# rings_v30.net
KiCad netlist of a schematic drawn in EAGLE
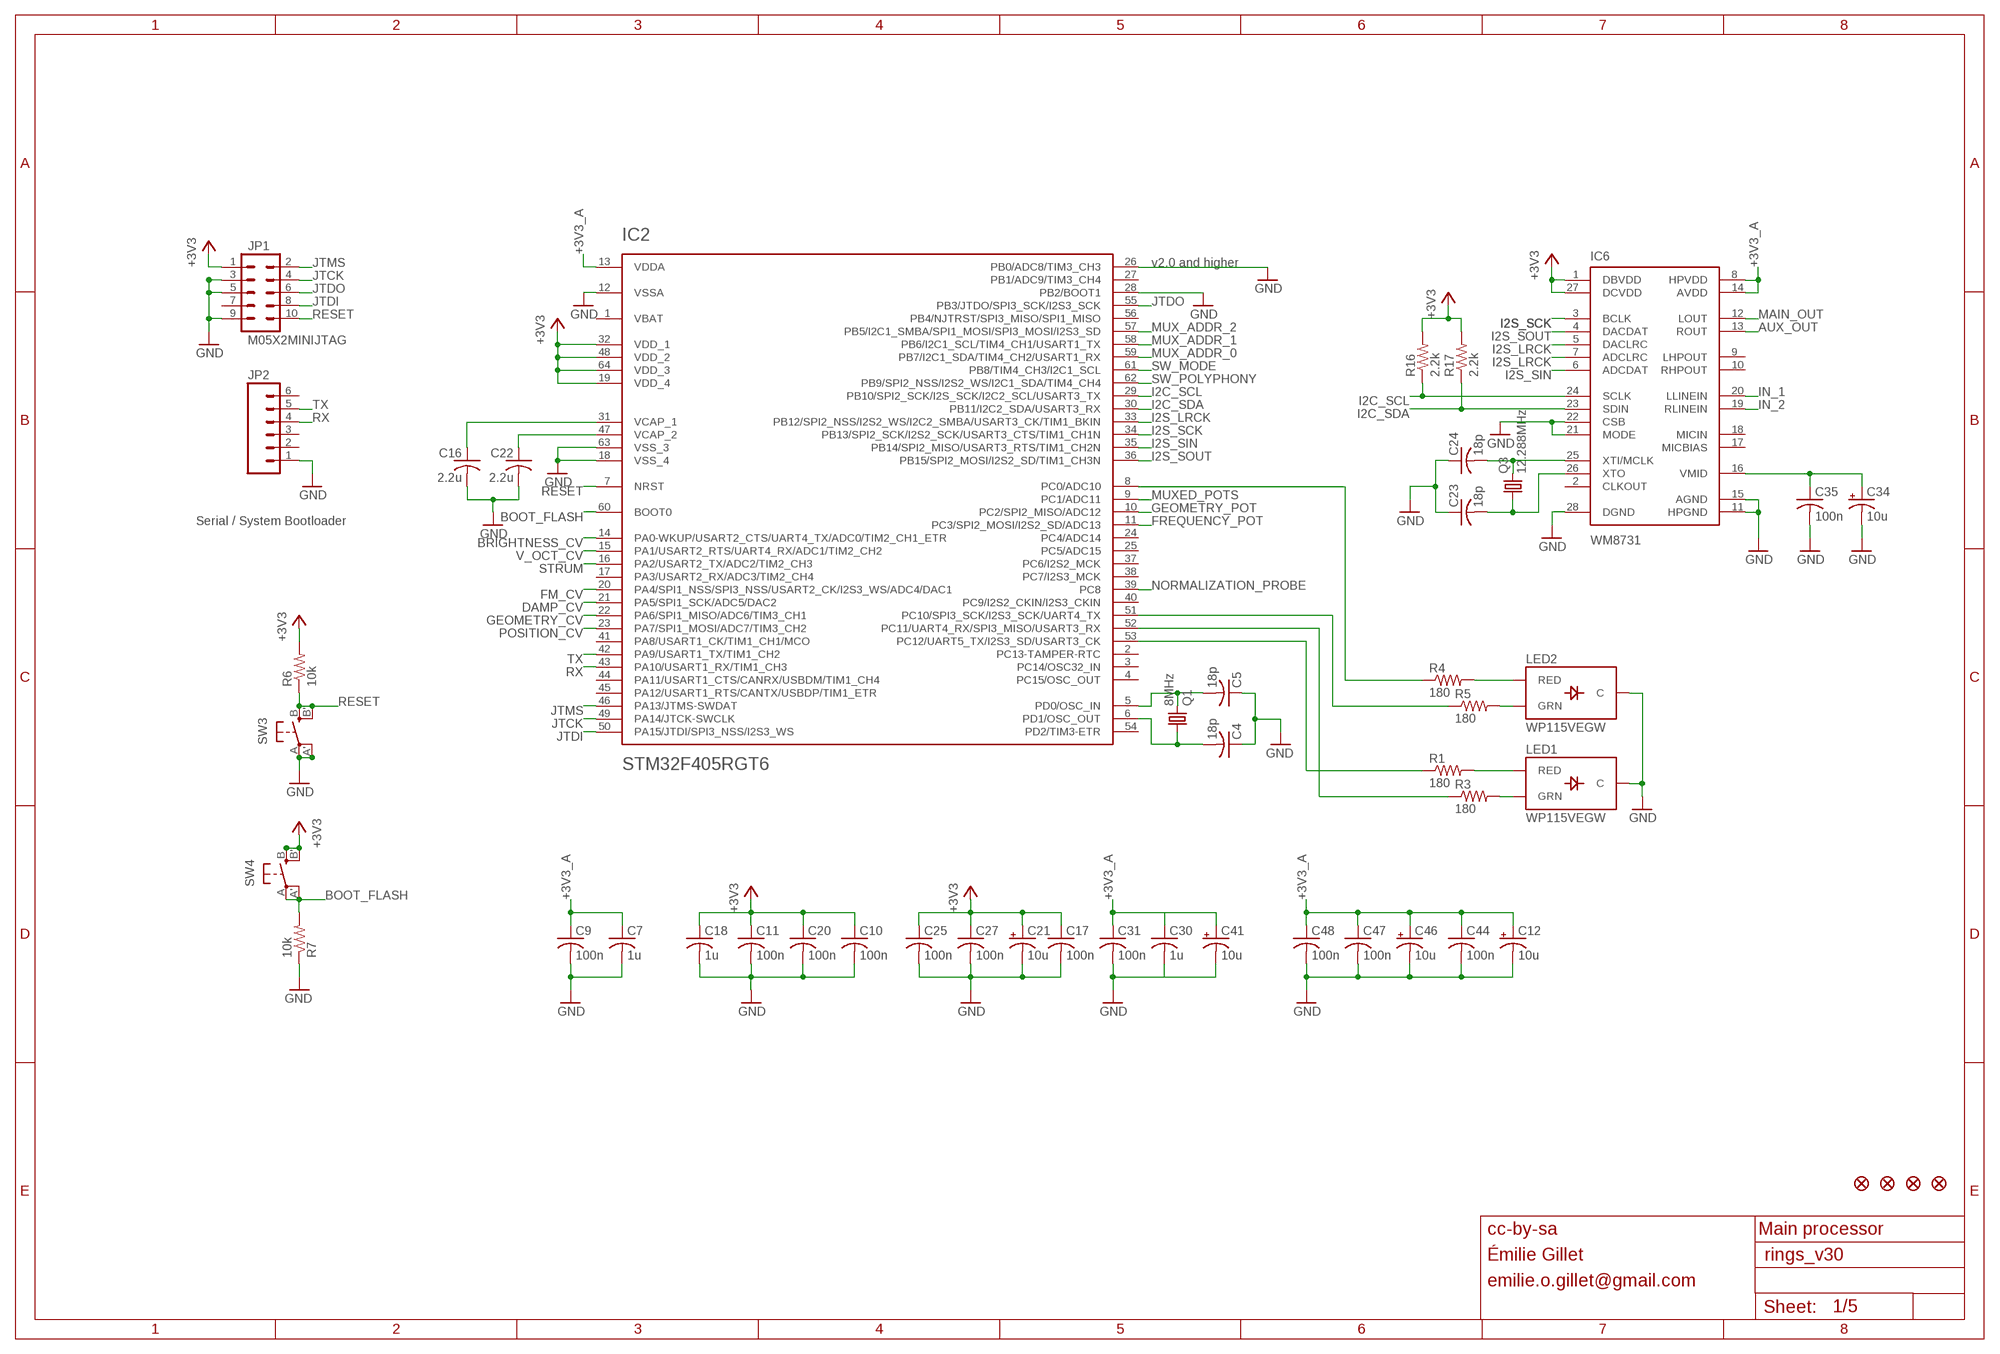
[diagram p0: schematic, sheet 1]
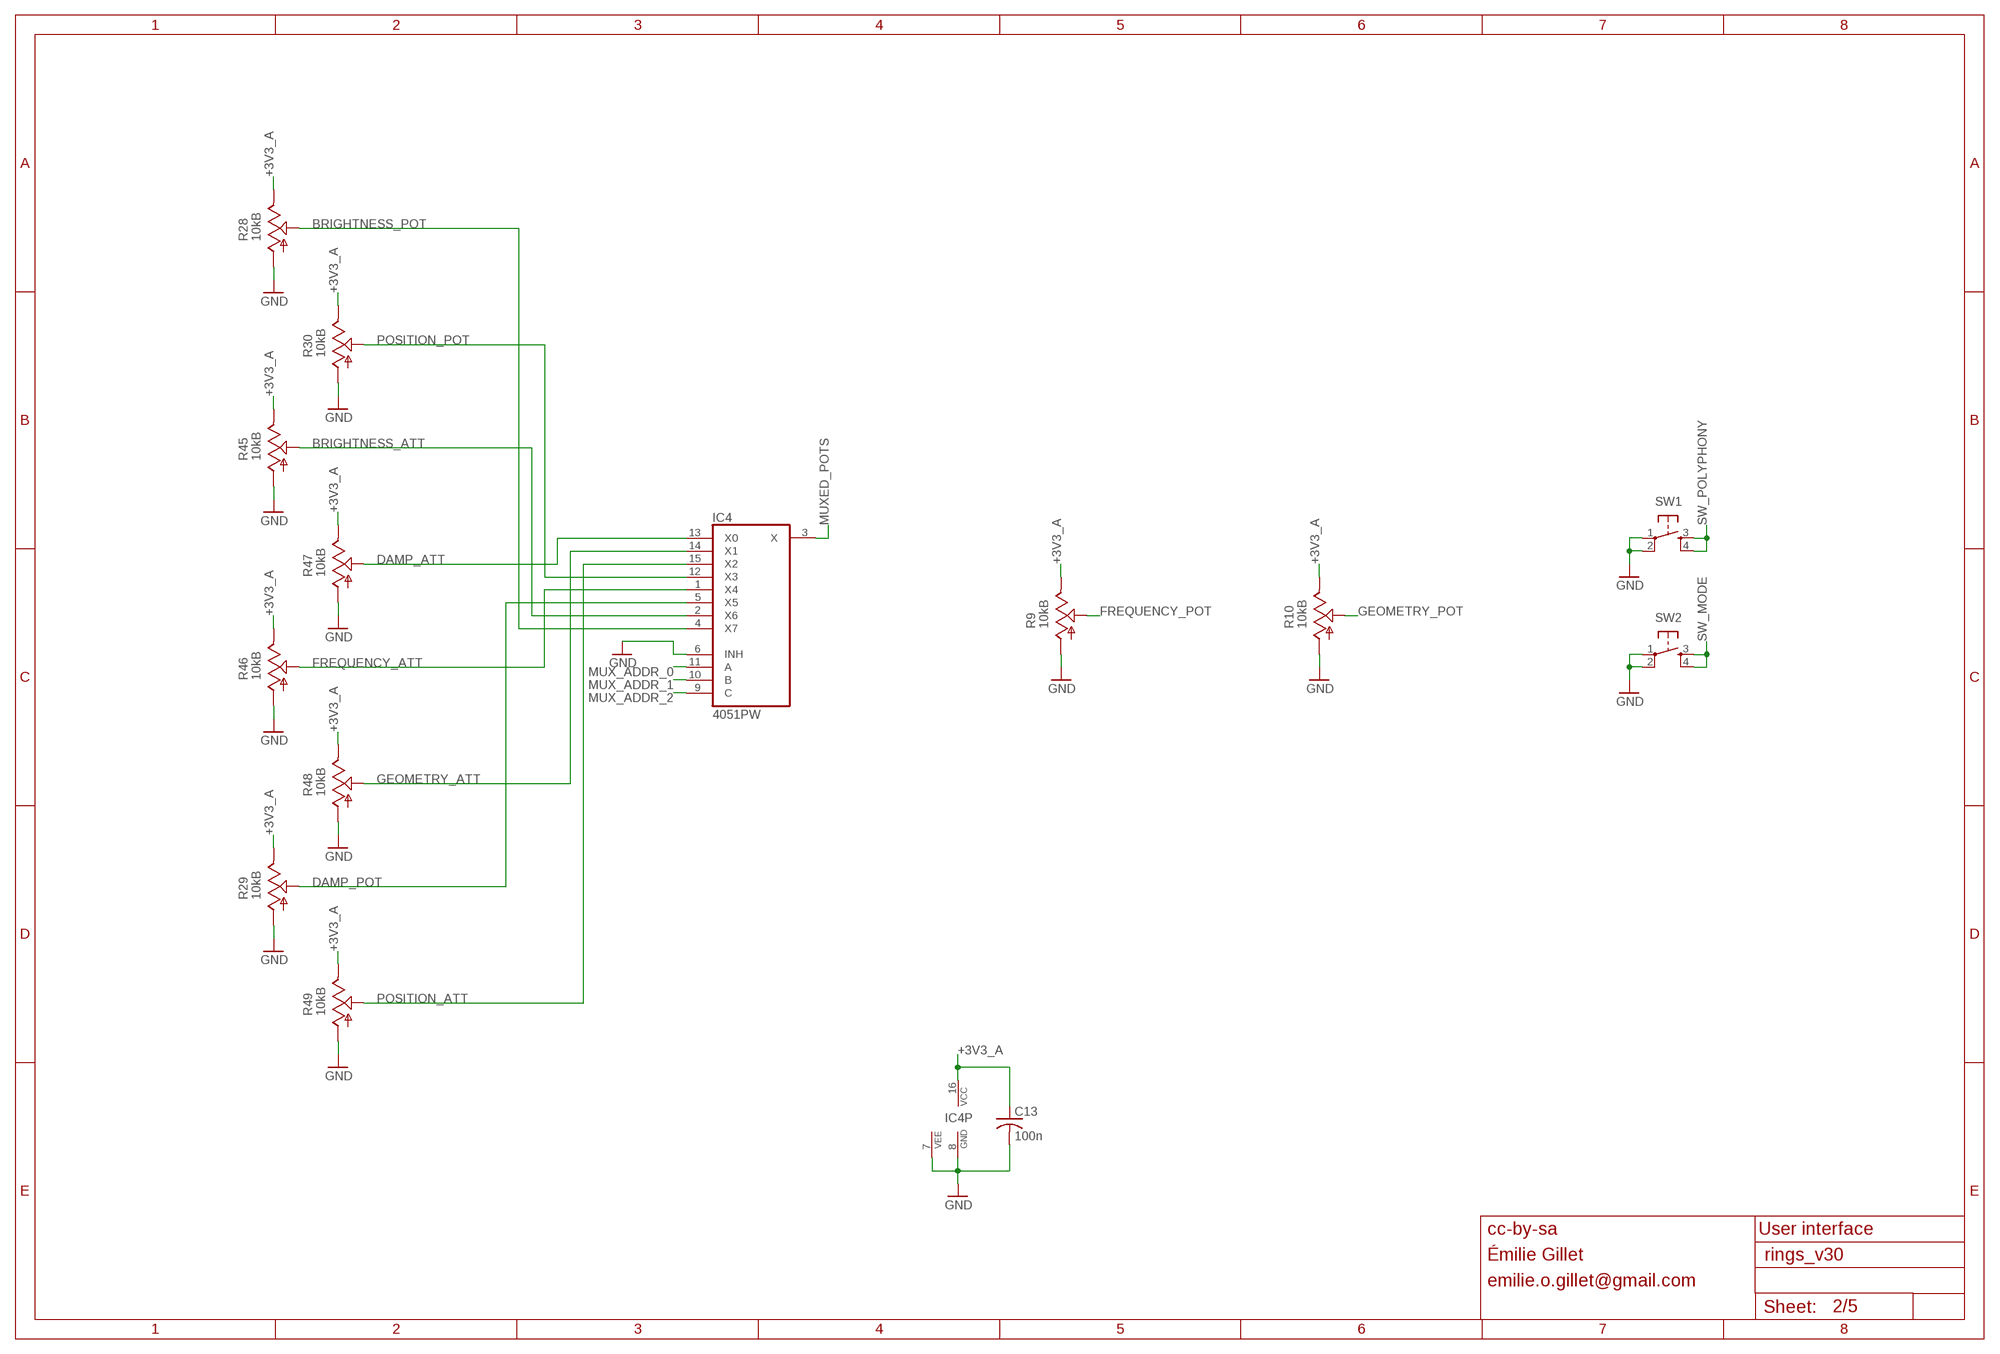
[diagram p1: schematic, sheet 2]
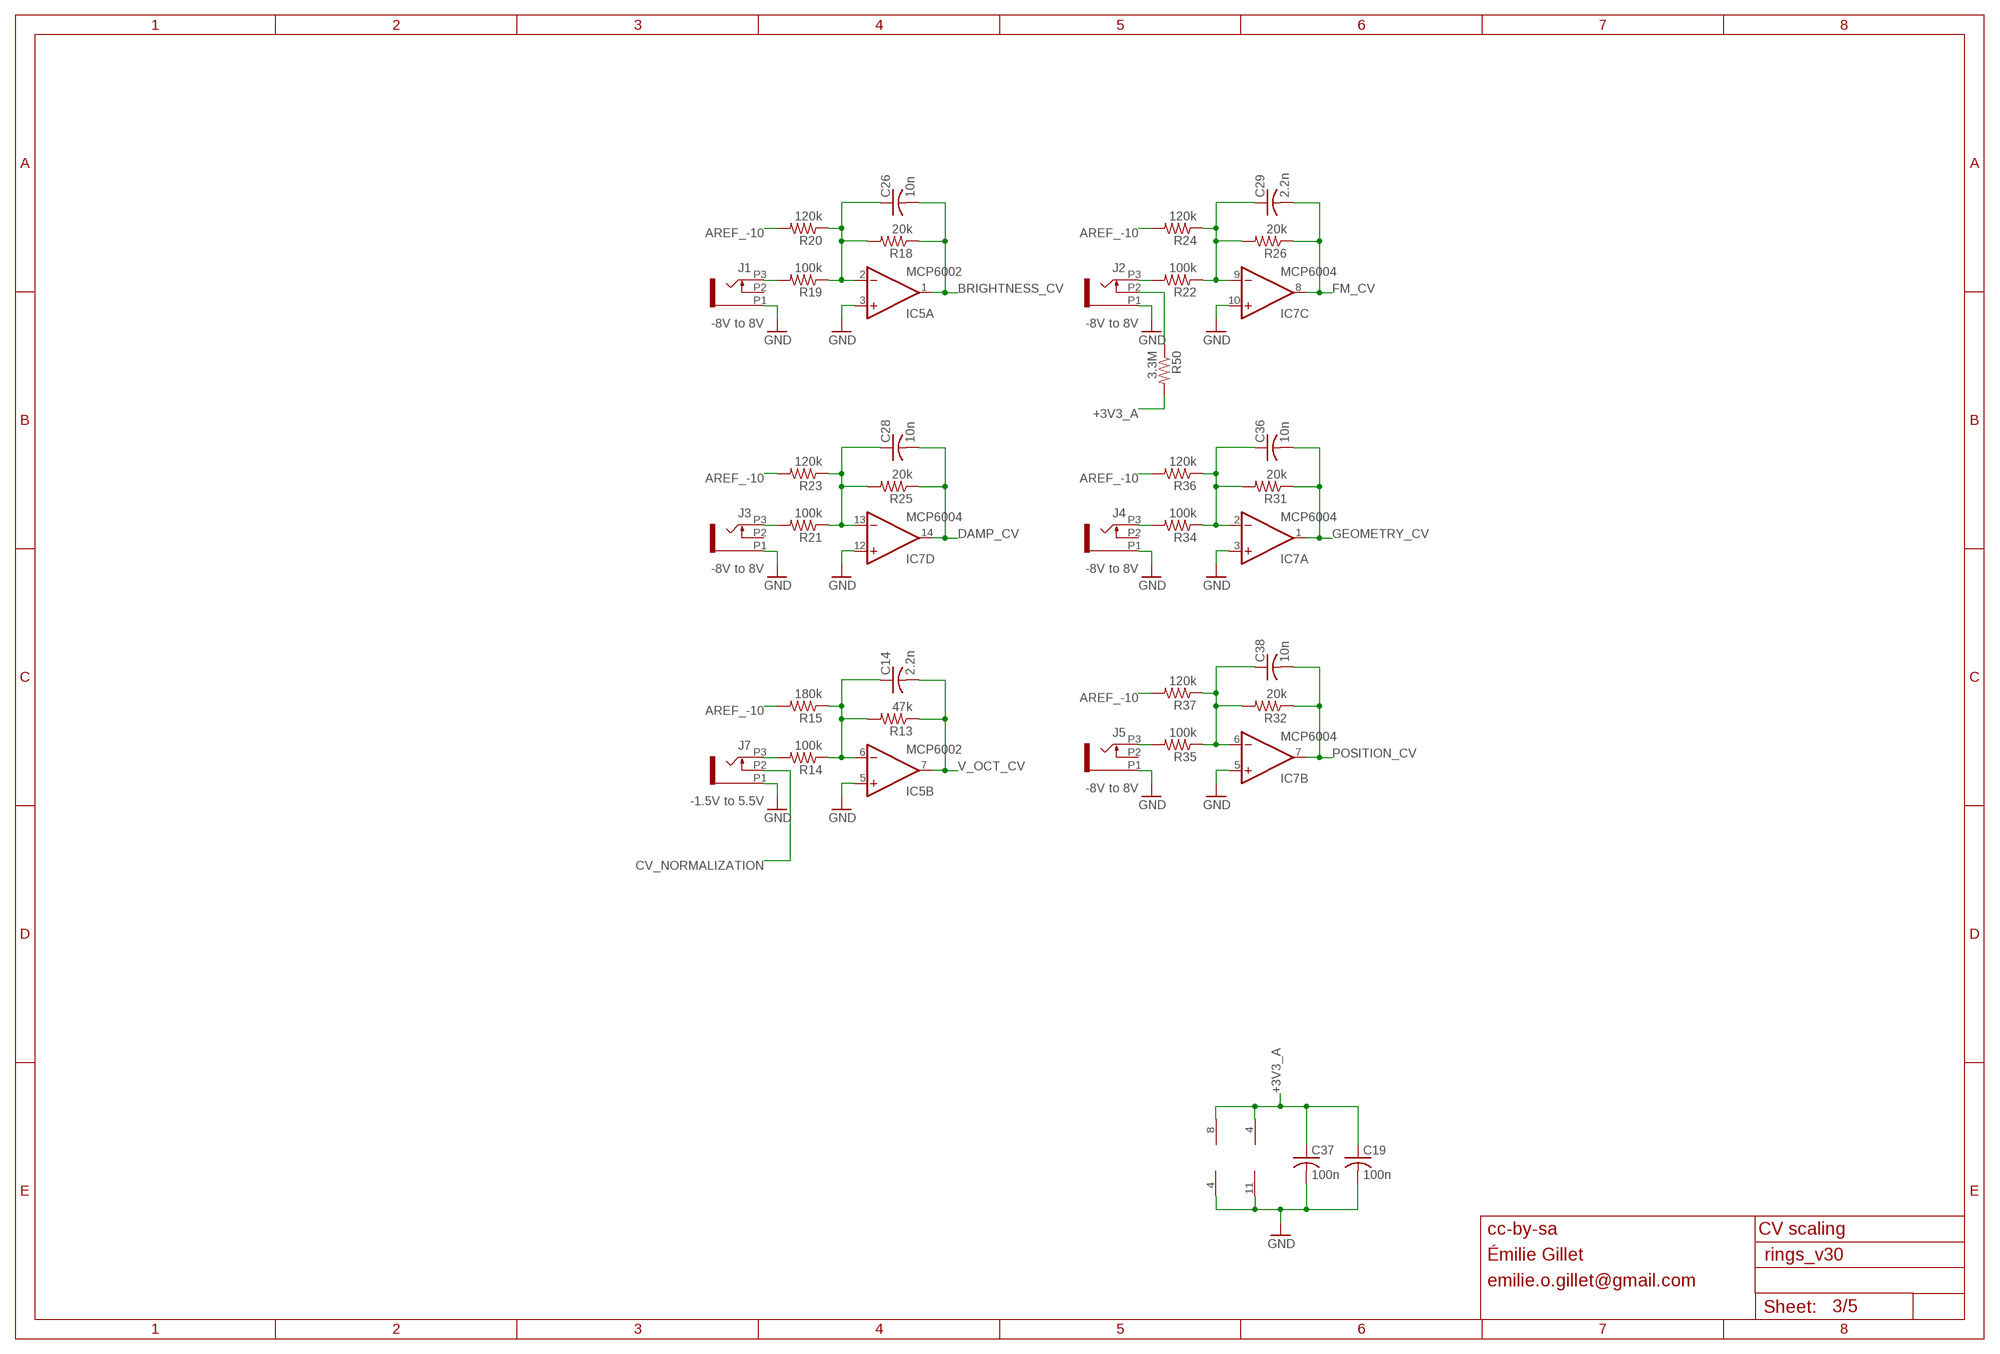
[diagram p2: schematic, sheet 3]
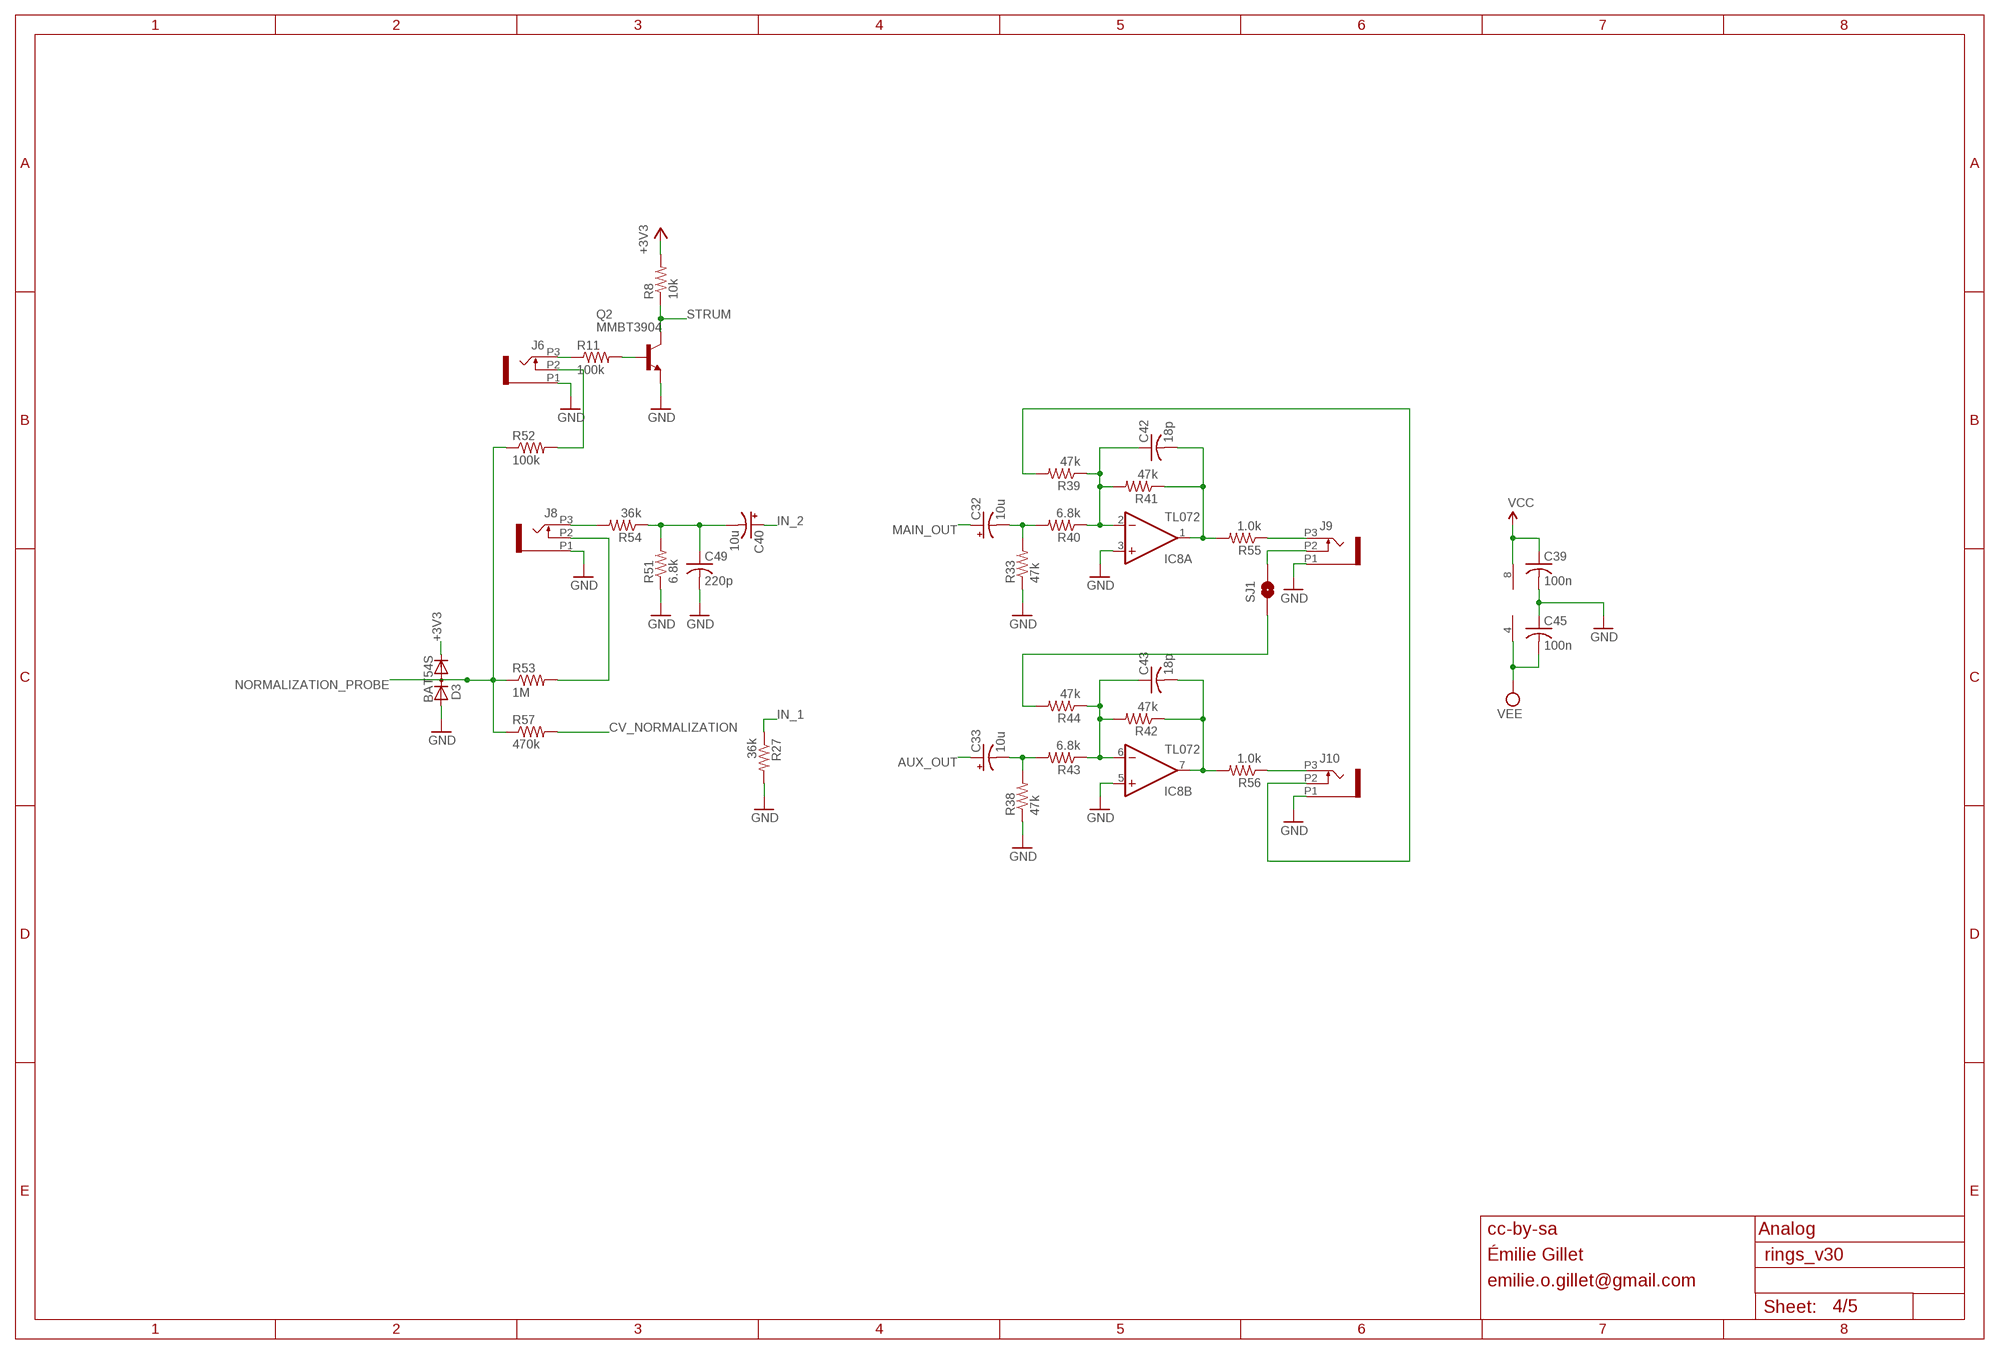
[diagram p3: schematic, sheet 4]
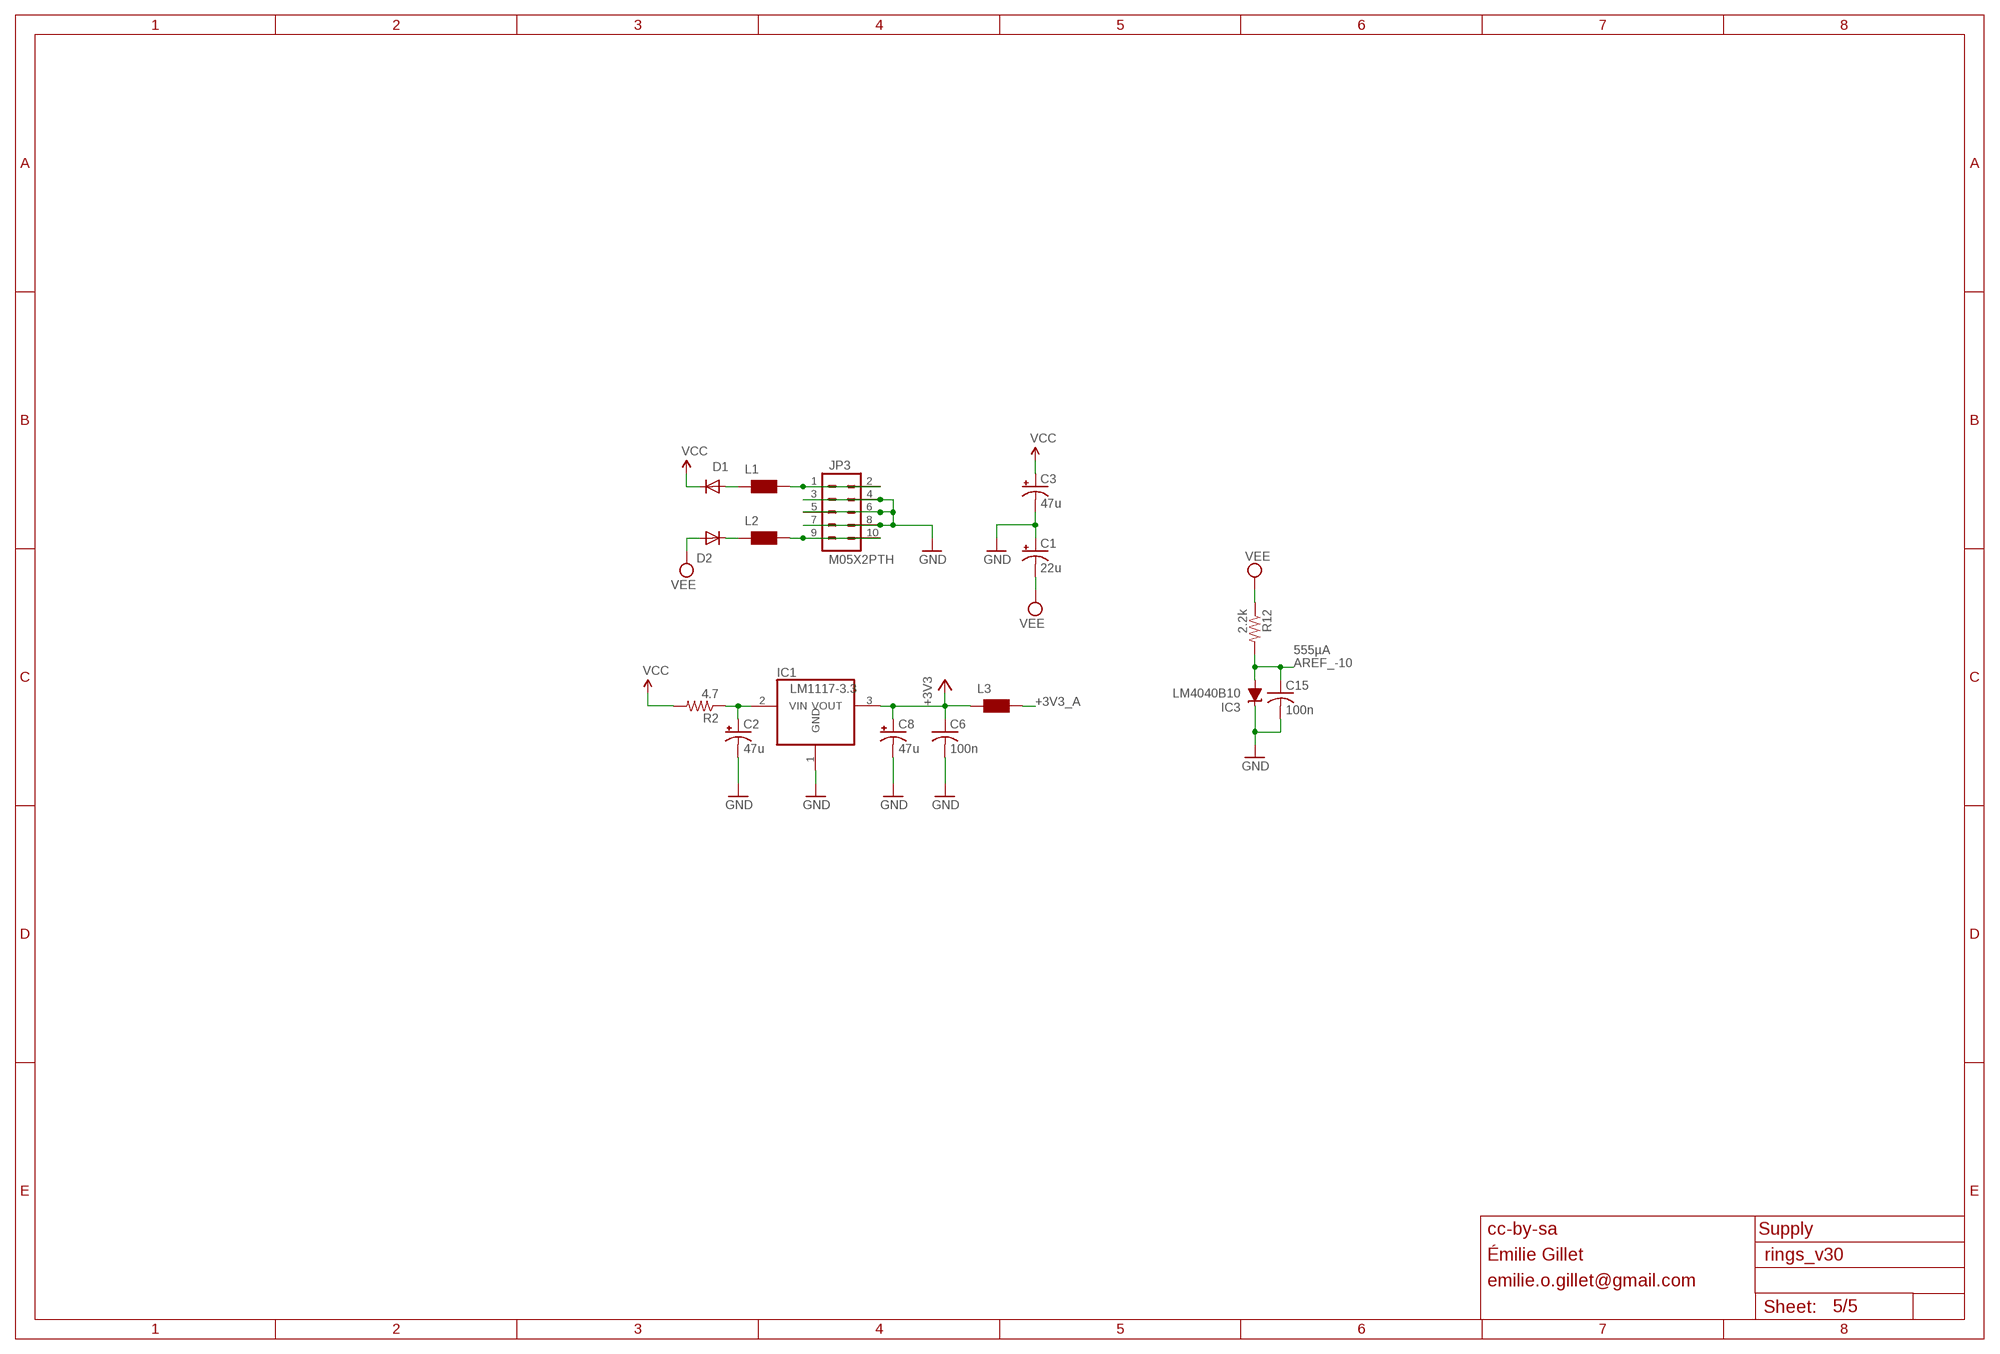
[diagram p4: schematic, sheet 5]

(export (version "E")
  (design (tool "Eeschema 10.0.6"))
  (components
    (comp (ref "C14")
      (value "2.2n")
      (footprint "eagle-import:C0603")
      (libsource (lib "eagle-import") (part "C-USC0603"))
    )
    (comp (ref "C19")
      (value "100n")
      (footprint "eagle-import:C0603")
      (libsource (lib "eagle-import") (part "C-USC0603"))
    )
    (comp (ref "C26")
      (value "10n")
      (footprint "eagle-import:C0603")
      (libsource (lib "eagle-import") (part "C-USC0603"))
    )
    (comp (ref "C28")
      (value "10n")
      (footprint "eagle-import:C0603")
      (libsource (lib "eagle-import") (part "C-USC0603"))
    )
    (comp (ref "C29")
      (value "2.2n")
      (footprint "eagle-import:C0603")
      (libsource (lib "eagle-import") (part "C-USC0603"))
    )
    (comp (ref "C36")
      (value "10n")
      (footprint "eagle-import:C0603")
      (libsource (lib "eagle-import") (part "C-USC0603"))
    )
    (comp (ref "C37")
      (value "100n")
      (footprint "eagle-import:C0603")
      (libsource (lib "eagle-import") (part "C-USC0603"))
    )
    (comp (ref "C38")
      (value "10n")
      (footprint "eagle-import:C0603")
      (libsource (lib "eagle-import") (part "C-USC0603"))
    )
    (comp (ref "IC5")
      (value "MCP6002")
      (footprint "eagle-import:SO08")
      (libsource (lib "eagle-import") (part "TL072D"))
    )
    (comp (ref "IC7")
      (value "MCP6004")
      (footprint "eagle-import:SO14")
      (libsource (lib "eagle-import") (part "TL074D"))
    )
    (comp (ref "J1")
      (value "PJ301_THONKICONN6")
      (footprint "eagle-import:WQP_PJ_301M6")
      (libsource (lib "eagle-import") (part "PJ301_THONKICONN6"))
    )
    (comp (ref "J2")
      (value "PJ301_THONKICONN6")
      (footprint "eagle-import:WQP_PJ_301M6")
      (libsource (lib "eagle-import") (part "PJ301_THONKICONN6"))
    )
    (comp (ref "J3")
      (value "PJ301_THONKICONN6")
      (footprint "eagle-import:WQP_PJ_301M6")
      (libsource (lib "eagle-import") (part "PJ301_THONKICONN6"))
    )
    (comp (ref "J4")
      (value "PJ301_THONKICONN6")
      (footprint "eagle-import:WQP_PJ_301M6")
      (libsource (lib "eagle-import") (part "PJ301_THONKICONN6"))
    )
    (comp (ref "J5")
      (value "PJ301_THONKICONN6")
      (footprint "eagle-import:WQP_PJ_301M6")
      (libsource (lib "eagle-import") (part "PJ301_THONKICONN6"))
    )
    (comp (ref "J7")
      (value "PJ301_THONKICONN6")
      (footprint "eagle-import:WQP_PJ_301M6")
      (libsource (lib "eagle-import") (part "PJ301_THONKICONN6"))
    )
    (comp (ref "R13")
      (value "47k")
      (footprint "eagle-import:R0603")
      (libsource (lib "eagle-import") (part "R-US_R0603"))
    )
    (comp (ref "R14")
      (value "100k")
      (footprint "eagle-import:R0603")
      (libsource (lib "eagle-import") (part "R-US_R0603"))
    )
    (comp (ref "R15")
      (value "180k")
      (footprint "eagle-import:R0603")
      (libsource (lib "eagle-import") (part "R-US_R0603"))
    )
    (comp (ref "R18")
      (value "20k")
      (footprint "eagle-import:R0603")
      (libsource (lib "eagle-import") (part "R-US_R0603"))
    )
    (comp (ref "R19")
      (value "100k")
      (footprint "eagle-import:R0603")
      (libsource (lib "eagle-import") (part "R-US_R0603"))
    )
    (comp (ref "R20")
      (value "120k")
      (footprint "eagle-import:R0603")
      (libsource (lib "eagle-import") (part "R-US_R0603"))
    )
    (comp (ref "R21")
      (value "100k")
      (footprint "eagle-import:R0603")
      (libsource (lib "eagle-import") (part "R-US_R0603"))
    )
    (comp (ref "R22")
      (value "100k")
      (footprint "eagle-import:R0603")
      (libsource (lib "eagle-import") (part "R-US_R0603"))
    )
    (comp (ref "R23")
      (value "120k")
      (footprint "eagle-import:R0603")
      (libsource (lib "eagle-import") (part "R-US_R0603"))
    )
    (comp (ref "R24")
      (value "120k")
      (footprint "eagle-import:R0603")
      (libsource (lib "eagle-import") (part "R-US_R0603"))
    )
    (comp (ref "R25")
      (value "20k")
      (footprint "eagle-import:R0603")
      (libsource (lib "eagle-import") (part "R-US_R0603"))
    )
    (comp (ref "R26")
      (value "20k")
      (footprint "eagle-import:R0603")
      (libsource (lib "eagle-import") (part "R-US_R0603"))
    )
    (comp (ref "R31")
      (value "20k")
      (footprint "eagle-import:R0603")
      (libsource (lib "eagle-import") (part "R-US_R0603"))
    )
    (comp (ref "R32")
      (value "20k")
      (footprint "eagle-import:R0603")
      (libsource (lib "eagle-import") (part "R-US_R0603"))
    )
    (comp (ref "R34")
      (value "100k")
      (footprint "eagle-import:R0603")
      (libsource (lib "eagle-import") (part "R-US_R0603"))
    )
    (comp (ref "R35")
      (value "100k")
      (footprint "eagle-import:R0603")
      (libsource (lib "eagle-import") (part "R-US_R0603"))
    )
    (comp (ref "R36")
      (value "120k")
      (footprint "eagle-import:R0603")
      (libsource (lib "eagle-import") (part "R-US_R0603"))
    )
    (comp (ref "R37")
      (value "120k")
      (footprint "eagle-import:R0603")
      (libsource (lib "eagle-import") (part "R-US_R0603"))
    )
    (comp (ref "R50")
      (value "3.3M")
      (footprint "eagle-import:R0603")
      (libsource (lib "eagle-import") (part "R-US_R0603"))
    )
    (comp (ref "C13")
      (value "100n")
      (footprint "eagle-import:C0603")
      (libsource (lib "eagle-import") (part "C-USC0603"))
    )
    (comp (ref "IC4")
      (value "4051PW")
      (footprint "eagle-import:TSSOP16")
      (libsource (lib "eagle-import") (part "4051PW"))
    )
    (comp (ref "R9")
      (value "10kB")
      (footprint "eagle-import:ALPS_POT_VERTICAL_PS")
      (libsource (lib "eagle-import") (part "POT_USVERTICAL_PS"))
    )
    (comp (ref "R10")
      (value "10kB")
      (footprint "eagle-import:ALPS_POT_VERTICAL_PS")
      (libsource (lib "eagle-import") (part "POT_USVERTICAL_PS"))
    )
    (comp (ref "R28")
      (value "10kB")
      (footprint "eagle-import:ALPS_POT_VERTICAL_PS")
      (libsource (lib "eagle-import") (part "POT_USVERTICAL_PS"))
    )
    (comp (ref "R29")
      (value "10kB")
      (footprint "eagle-import:ALPS_POT_VERTICAL_PS")
      (libsource (lib "eagle-import") (part "POT_USVERTICAL_PS"))
    )
    (comp (ref "R30")
      (value "10kB")
      (footprint "eagle-import:ALPS_POT_VERTICAL_PS")
      (libsource (lib "eagle-import") (part "POT_USVERTICAL_PS"))
    )
    (comp (ref "R45")
      (value "10kB")
      (footprint "eagle-import:ALPS_POT_VERTICAL")
      (libsource (lib "eagle-import") (part "POT_USVERTICAL"))
    )
    (comp (ref "R46")
      (value "10kB")
      (footprint "eagle-import:ALPS_POT_VERTICAL")
      (libsource (lib "eagle-import") (part "POT_USVERTICAL"))
    )
    (comp (ref "R47")
      (value "10kB")
      (footprint "eagle-import:ALPS_POT_VERTICAL")
      (libsource (lib "eagle-import") (part "POT_USVERTICAL"))
    )
    (comp (ref "R48")
      (value "10kB")
      (footprint "eagle-import:ALPS_POT_VERTICAL")
      (libsource (lib "eagle-import") (part "POT_USVERTICAL"))
    )
    (comp (ref "R49")
      (value "10kB")
      (footprint "eagle-import:ALPS_POT_VERTICAL")
      (libsource (lib "eagle-import") (part "POT_USVERTICAL"))
    )
    (comp (ref "SW1")
      (value "TAC_SWITCHPTH")
      (footprint "eagle-import:TACTILE-PTH")
      (libsource (lib "eagle-import") (part "TAC_SWITCHPTH"))
    )
    (comp (ref "SW2")
      (value "TAC_SWITCHPTH")
      (footprint "eagle-import:TACTILE-PTH")
      (libsource (lib "eagle-import") (part "TAC_SWITCHPTH"))
    )
    (comp (ref "C1")
      (value "22u")
      (footprint "eagle-import:PANASONIC_C")
      (libsource (lib "eagle-import") (part "CPOL-USC"))
    )
    (comp (ref "C2")
      (value "47u")
      (footprint "eagle-import:PANASONIC_D")
      (libsource (lib "eagle-import") (part "CPOL-USD"))
    )
    (comp (ref "C3")
      (value "47u")
      (footprint "eagle-import:PANASONIC_D")
      (libsource (lib "eagle-import") (part "CPOL-USD"))
    )
    (comp (ref "C6")
      (value "100n")
      (footprint "eagle-import:C0603")
      (libsource (lib "eagle-import") (part "C-USC0603"))
    )
    (comp (ref "C8")
      (value "47u")
      (footprint "eagle-import:PANASONIC_D")
      (libsource (lib "eagle-import") (part "CPOL-USD"))
    )
    (comp (ref "C15")
      (value "100n")
      (footprint "eagle-import:C0603")
      (libsource (lib "eagle-import") (part "C-USC0603"))
    )
    (comp (ref "D1")
      (value "1N5819HW")
      (footprint "eagle-import:SOD123")
      (libsource (lib "eagle-import") (part "DIODE-SOD123"))
    )
    (comp (ref "D2")
      (value "1N5819HW")
      (footprint "eagle-import:SOD123")
      (libsource (lib "eagle-import") (part "DIODE-SOD123"))
    )
    (comp (ref "IC1")
      (value "LM1117-3.3")
      (footprint "eagle-import:TO252")
      (libsource (lib "eagle-import") (part "REG1117T"))
    )
    (comp (ref "IC3")
      (value "LM4040B10")
      (footprint "eagle-import:DBZ_R-PDSO-G3")
      (libsource (lib "eagle-import") (part "LM4041DBZB12"))
    )
    (comp (ref "JP3")
      (value "M05X2PTH")
      (footprint "eagle-import:AVR_ICSP")
      (libsource (lib "eagle-import") (part "M05X2PTH"))
    )
    (comp (ref "L1")
      (value "WE-CBF_0603")
      (footprint "eagle-import:0603")
      (libsource (lib "eagle-import") (part "WE-CBF_0603"))
    )
    (comp (ref "L2")
      (value "WE-CBF_0603")
      (footprint "eagle-import:0603")
      (libsource (lib "eagle-import") (part "WE-CBF_0603"))
    )
    (comp (ref "L3")
      (value "WE-CBF_0603")
      (footprint "eagle-import:0603")
      (libsource (lib "eagle-import") (part "WE-CBF_0603"))
    )
    (comp (ref "R2")
      (value "4.7")
      (footprint "eagle-import:R1206")
      (libsource (lib "eagle-import") (part "R-US_R1206"))
    )
    (comp (ref "R12")
      (value "2.2k")
      (footprint "eagle-import:R0603")
      (libsource (lib "eagle-import") (part "R-US_R0603"))
    )
    (comp (ref "C4")
      (value "18p")
      (footprint "eagle-import:C0603")
      (libsource (lib "eagle-import") (part "C-USC0603"))
    )
    (comp (ref "C5")
      (value "18p")
      (footprint "eagle-import:C0603")
      (libsource (lib "eagle-import") (part "C-USC0603"))
    )
    (comp (ref "C7")
      (value "1u")
      (footprint "eagle-import:C0603")
      (libsource (lib "eagle-import") (part "C-USC0603"))
    )
    (comp (ref "C9")
      (value "100n")
      (footprint "eagle-import:C0603")
      (libsource (lib "eagle-import") (part "C-USC0603"))
    )
    (comp (ref "C10")
      (value "100n")
      (footprint "eagle-import:C0603")
      (libsource (lib "eagle-import") (part "C-USC0603"))
    )
    (comp (ref "C11")
      (value "100n")
      (footprint "eagle-import:C0603")
      (libsource (lib "eagle-import") (part "C-USC0603"))
    )
    (comp (ref "C12")
      (value "10u")
      (footprint "eagle-import:PANASONIC_A")
      (libsource (lib "eagle-import") (part "CPOL-USA"))
    )
    (comp (ref "C16")
      (value "2.2u")
      (footprint "eagle-import:C0805")
      (libsource (lib "eagle-import") (part "C-USC0805"))
    )
    (comp (ref "C17")
      (value "100n")
      (footprint "eagle-import:C0603")
      (libsource (lib "eagle-import") (part "C-USC0603"))
    )
    (comp (ref "C18")
      (value "1u")
      (footprint "eagle-import:C0603")
      (libsource (lib "eagle-import") (part "C-USC0603"))
    )
    (comp (ref "C20")
      (value "100n")
      (footprint "eagle-import:C0603")
      (libsource (lib "eagle-import") (part "C-USC0603"))
    )
    (comp (ref "C21")
      (value "10u")
      (footprint "eagle-import:PANASONIC_A")
      (libsource (lib "eagle-import") (part "CPOL-USA"))
    )
    (comp (ref "C22")
      (value "2.2u")
      (footprint "eagle-import:C0805")
      (libsource (lib "eagle-import") (part "C-USC0805"))
    )
    (comp (ref "C23")
      (value "18p")
      (footprint "eagle-import:C0603")
      (libsource (lib "eagle-import") (part "C-USC0603"))
    )
    (comp (ref "C24")
      (value "18p")
      (footprint "eagle-import:C0603")
      (libsource (lib "eagle-import") (part "C-USC0603"))
    )
    (comp (ref "C25")
      (value "100n")
      (footprint "eagle-import:C0603")
      (libsource (lib "eagle-import") (part "C-USC0603"))
    )
    (comp (ref "C27")
      (value "100n")
      (footprint "eagle-import:C0603")
      (libsource (lib "eagle-import") (part "C-USC0603"))
    )
    (comp (ref "C30")
      (value "1u")
      (footprint "eagle-import:C0603")
      (libsource (lib "eagle-import") (part "C-USC0603"))
    )
    (comp (ref "C31")
      (value "100n")
      (footprint "eagle-import:C0603")
      (libsource (lib "eagle-import") (part "C-USC0603"))
    )
    (comp (ref "C34")
      (value "10u")
      (footprint "eagle-import:PANASONIC_A")
      (libsource (lib "eagle-import") (part "CPOL-USA"))
    )
    (comp (ref "C35")
      (value "100n")
      (footprint "eagle-import:C0603")
      (libsource (lib "eagle-import") (part "C-USC0603"))
    )
    (comp (ref "C41")
      (value "10u")
      (footprint "eagle-import:PANASONIC_A")
      (libsource (lib "eagle-import") (part "CPOL-USA"))
    )
    (comp (ref "C44")
      (value "100n")
      (footprint "eagle-import:C0603")
      (libsource (lib "eagle-import") (part "C-USC0603"))
    )
    (comp (ref "C46")
      (value "10u")
      (footprint "eagle-import:PANASONIC_A")
      (libsource (lib "eagle-import") (part "CPOL-USA"))
    )
    (comp (ref "C47")
      (value "100n")
      (footprint "eagle-import:C0603")
      (libsource (lib "eagle-import") (part "C-USC0603"))
    )
    (comp (ref "C48")
      (value "100n")
      (footprint "eagle-import:C0603")
      (libsource (lib "eagle-import") (part "C-USC0603"))
    )
    (comp (ref "F1")
      (value "FIDUCIAL1X2")
      (footprint "eagle-import:FIDUCIAL-1X2")
      (libsource (lib "eagle-import") (part "FIDUCIAL1X2"))
    )
    (comp (ref "F2")
      (value "FIDUCIAL1X2")
      (footprint "eagle-import:FIDUCIAL-1X2")
      (libsource (lib "eagle-import") (part "FIDUCIAL1X2"))
    )
    (comp (ref "F3")
      (value "FIDUCIAL1X2")
      (footprint "eagle-import:FIDUCIAL-1X2")
      (libsource (lib "eagle-import") (part "FIDUCIAL1X2"))
    )
    (comp (ref "F4")
      (value "FIDUCIAL1X2")
      (footprint "eagle-import:FIDUCIAL-1X2")
      (libsource (lib "eagle-import") (part "FIDUCIAL1X2"))
    )
    (comp (ref "IC2")
      (value "STM32F405RGT6")
      (footprint "eagle-import:TQFP-10X10-64")
      (libsource (lib "eagle-import") (part "STM32F20X"))
    )
    (comp (ref "IC6")
      (value "WM8731")
      (footprint "eagle-import:SSOP28")
      (libsource (lib "eagle-import") (part "WM8731"))
    )
    (comp (ref "JP1")
      (value "M05X2MINIJTAG")
      (footprint "eagle-import:2X5-1.27")
      (libsource (lib "eagle-import") (part "M05X2MINIJTAG"))
    )
    (comp (ref "JP2")
      (value "M06SIP")
      (footprint "eagle-import:1X06")
      (libsource (lib "eagle-import") (part "M06SIP"))
    )
    (comp (ref "LED1")
      (value "WP115VEGW")
      (footprint "eagle-import:LED-BICOLOR-THROUGHHOLE")
      (libsource (lib "eagle-import") (part "LED-BICOLOR-THROUGHHOLE"))
    )
    (comp (ref "LED2")
      (value "WP115VEGW")
      (footprint "eagle-import:LED-BICOLOR-THROUGHHOLE")
      (libsource (lib "eagle-import") (part "LED-BICOLOR-THROUGHHOLE"))
    )
    (comp (ref "Q1")
      (value "8MHz")
      (footprint "eagle-import:HC49UP")
      (libsource (lib "eagle-import") (part "CRYSTALHC49UP"))
    )
    (comp (ref "Q3")
      (value "12.288MHz")
      (footprint "eagle-import:HC49UP")
      (libsource (lib "eagle-import") (part "CRYSTALHC49UP"))
    )
    (comp (ref "R1")
      (value "180")
      (footprint "eagle-import:R0603")
      (libsource (lib "eagle-import") (part "R-US_R0603"))
    )
    (comp (ref "R3")
      (value "180")
      (footprint "eagle-import:R0603")
      (libsource (lib "eagle-import") (part "R-US_R0603"))
    )
    (comp (ref "R4")
      (value "180")
      (footprint "eagle-import:R0603")
      (libsource (lib "eagle-import") (part "R-US_R0603"))
    )
    (comp (ref "R5")
      (value "180")
      (footprint "eagle-import:R0603")
      (libsource (lib "eagle-import") (part "R-US_R0603"))
    )
    (comp (ref "R6")
      (value "10k")
      (footprint "eagle-import:R0603")
      (libsource (lib "eagle-import") (part "R-US_R0603"))
    )
    (comp (ref "R7")
      (value "10k")
      (footprint "eagle-import:R0603")
      (libsource (lib "eagle-import") (part "R-US_R0603"))
    )
    (comp (ref "R16")
      (value "2.2k")
      (footprint "eagle-import:R0603")
      (libsource (lib "eagle-import") (part "R-US_R0603"))
    )
    (comp (ref "R17")
      (value "2.2k")
      (footprint "eagle-import:R0603")
      (libsource (lib "eagle-import") (part "R-US_R0603"))
    )
    (comp (ref "SW3")
      (value "EVQQ2")
      (footprint "eagle-import:EVQ-Q2")
      (libsource (lib "eagle-import") (part "EVQQ2"))
    )
    (comp (ref "SW4")
      (value "EVQQ2")
      (footprint "eagle-import:EVQ-Q2")
      (libsource (lib "eagle-import") (part "EVQQ2"))
    )
    (comp (ref "C32")
      (value "10u")
      (footprint "eagle-import:PANASONIC_A")
      (libsource (lib "eagle-import") (part "CPOL-USA"))
    )
    (comp (ref "C33")
      (value "10u")
      (footprint "eagle-import:PANASONIC_A")
      (libsource (lib "eagle-import") (part "CPOL-USA"))
    )
    (comp (ref "C39")
      (value "100n")
      (footprint "eagle-import:C0603")
      (libsource (lib "eagle-import") (part "C-USC0603"))
    )
    (comp (ref "C40")
      (value "10u")
      (footprint "eagle-import:PANASONIC_A")
      (libsource (lib "eagle-import") (part "CPOL-USA"))
    )
    (comp (ref "C42")
      (value "18p")
      (footprint "eagle-import:C0603")
      (libsource (lib "eagle-import") (part "C-USC0603"))
    )
    (comp (ref "C43")
      (value "18p")
      (footprint "eagle-import:C0603")
      (libsource (lib "eagle-import") (part "C-USC0603"))
    )
    (comp (ref "C45")
      (value "100n")
      (footprint "eagle-import:C0603")
      (libsource (lib "eagle-import") (part "C-USC0603"))
    )
    (comp (ref "C49")
      (value "220p")
      (footprint "eagle-import:C0603")
      (libsource (lib "eagle-import") (part "C-USC0603"))
    )
    (comp (ref "D3")
      (value "BAT54S")
      (footprint "eagle-import:SOT23")
      (libsource (lib "eagle-import") (part "DIODE_2CACA-SOT23"))
    )
    (comp (ref "IC8")
      (value "TL072")
      (footprint "eagle-import:SO08")
      (libsource (lib "eagle-import") (part "og-linear_TL072D"))
    )
    (comp (ref "J6")
      (value "PJ301_THONKICONN6")
      (footprint "eagle-import:WQP_PJ_301M6")
      (libsource (lib "eagle-import") (part "PJ301_THONKICONN6"))
    )
    (comp (ref "J8")
      (value "PJ301_THONKICONN6")
      (footprint "eagle-import:WQP_PJ_301M6")
      (libsource (lib "eagle-import") (part "PJ301_THONKICONN6"))
    )
    (comp (ref "J9")
      (value "PJ301_THONKICONN6")
      (footprint "eagle-import:WQP_PJ_301M6")
      (libsource (lib "eagle-import") (part "PJ301_THONKICONN6"))
    )
    (comp (ref "J10")
      (value "PJ301_THONKICONN6")
      (footprint "eagle-import:WQP_PJ_301M6")
      (libsource (lib "eagle-import") (part "PJ301_THONKICONN6"))
    )
    (comp (ref "Q2")
      (value "MMBT3904")
      (footprint "eagle-import:SOT23-BEC")
      (libsource (lib "eagle-import") (part "-NPN-SOT23-BECMMBT3904LT1"))
    )
    (comp (ref "R8")
      (value "10k")
      (footprint "eagle-import:R0603")
      (libsource (lib "eagle-import") (part "R-US_R0603"))
    )
    (comp (ref "R11")
      (value "100k")
      (footprint "eagle-import:R0603")
      (libsource (lib "eagle-import") (part "R-US_R0603"))
    )
    (comp (ref "R27")
      (value "36k")
      (footprint "eagle-import:R0603")
      (libsource (lib "eagle-import") (part "R-US_R0603"))
    )
    (comp (ref "R33")
      (value "47k")
      (footprint "eagle-import:R0603")
      (libsource (lib "eagle-import") (part "R-US_R0603"))
    )
    (comp (ref "R38")
      (value "47k")
      (footprint "eagle-import:R0603")
      (libsource (lib "eagle-import") (part "R-US_R0603"))
    )
    (comp (ref "R39")
      (value "47k")
      (footprint "eagle-import:R0603")
      (libsource (lib "eagle-import") (part "R-US_R0603"))
    )
    (comp (ref "R40")
      (value "6.8k")
      (footprint "eagle-import:R0603")
      (libsource (lib "eagle-import") (part "R-US_R0603"))
    )
    (comp (ref "R41")
      (value "47k")
      (footprint "eagle-import:R0603")
      (libsource (lib "eagle-import") (part "R-US_R0603"))
    )
    (comp (ref "R42")
      (value "47k")
      (footprint "eagle-import:R0603")
      (libsource (lib "eagle-import") (part "R-US_R0603"))
    )
    (comp (ref "R43")
      (value "6.8k")
      (footprint "eagle-import:R0603")
      (libsource (lib "eagle-import") (part "R-US_R0603"))
    )
    (comp (ref "R44")
      (value "47k")
      (footprint "eagle-import:R0603")
      (libsource (lib "eagle-import") (part "R-US_R0603"))
    )
    (comp (ref "R51")
      (value "6.8k")
      (footprint "eagle-import:R0603")
      (libsource (lib "eagle-import") (part "R-US_R0603"))
    )
    (comp (ref "R52")
      (value "100k")
      (footprint "eagle-import:R0603")
      (libsource (lib "eagle-import") (part "R-US_R0603"))
    )
    (comp (ref "R53")
      (value "1M")
      (footprint "eagle-import:R0603")
      (libsource (lib "eagle-import") (part "R-US_R0603"))
    )
    (comp (ref "R54")
      (value "36k")
      (footprint "eagle-import:R0603")
      (libsource (lib "eagle-import") (part "R-US_R0603"))
    )
    (comp (ref "R55")
      (value "1.0k")
      (footprint "eagle-import:R0603")
      (libsource (lib "eagle-import") (part "R-US_R0603"))
    )
    (comp (ref "R56")
      (value "1.0k")
      (footprint "eagle-import:R0603")
      (libsource (lib "eagle-import") (part "R-US_R0603"))
    )
    (comp (ref "R57")
      (value "470k")
      (footprint "eagle-import:R0603")
      (libsource (lib "eagle-import") (part "R-US_R0603"))
    )
    (comp (ref "SJ1")
      (value "SOLDERJUMPERNC2")
      (footprint "eagle-import:SJ_2S-NOTRACE")
      (libsource (lib "eagle-import") (part "SOLDERJUMPERNC2"))
    )
  )
  (nets
    (net (code "1") (name "+3V3") (class "Default")
      (node (ref "C10") (pin "1") (pinfunction "1_1") (pintype "passive"))
      (node (ref "C11") (pin "1") (pinfunction "1_1") (pintype "passive"))
      (node (ref "C17") (pin "1") (pinfunction "1_1") (pintype "passive"))
      (node (ref "C18") (pin "1") (pinfunction "1_1") (pintype "passive"))
      (node (ref "C20") (pin "1") (pinfunction "1_1") (pintype "passive"))
      (node (ref "C21") (pin "+") (pinfunction "+_+") (pintype "passive"))
      (node (ref "C25") (pin "1") (pinfunction "1_1") (pintype "passive"))
      (node (ref "C27") (pin "1") (pinfunction "1_1") (pintype "passive"))
      (node (ref "C6") (pin "1") (pinfunction "1_1") (pintype "passive"))
      (node (ref "C8") (pin "+") (pinfunction "+_+") (pintype "passive"))
      (node (ref "D3") (pin "2") (pinfunction "C_2") (pintype "passive"))
      (node (ref "IC1") (pin "3") (pinfunction "VOUT_3") (pintype "output"))
      (node (ref "IC2") (pin "19") (pinfunction "VDD_4_19") (pintype "power_in"))
      (node (ref "IC2") (pin "32") (pinfunction "VDD_1_32") (pintype "power_in"))
      (node (ref "IC2") (pin "48") (pinfunction "VDD_2_48") (pintype "power_in"))
      (node (ref "IC2") (pin "64") (pinfunction "VDD_3_64") (pintype "power_in"))
      (node (ref "IC6") (pin "1") (pinfunction "DBVDD_1") (pintype "bidirectional"))
      (node (ref "IC6") (pin "27") (pinfunction "DCVDD_27") (pintype "bidirectional"))
      (node (ref "JP1") (pin "1") (pinfunction "1_1") (pintype "passive"))
      (node (ref "L3") (pin "1") (pinfunction "1_1") (pintype "passive"))
      (node (ref "R16") (pin "2") (pinfunction "2_2") (pintype "passive"))
      (node (ref "R17") (pin "2") (pinfunction "2_2") (pintype "passive"))
      (node (ref "R6") (pin "2") (pinfunction "2_2") (pintype "passive"))
      (node (ref "R8") (pin "2") (pinfunction "2_2") (pintype "passive"))
      (node (ref "SW4") (pin "B") (pinfunction "S_B") (pintype "passive"))
      (node (ref "SW4") (pin "B'") (pinfunction "S1_B'") (pintype "passive"))
    )
    (net (code "2") (name "+3V3_A") (class "Default")
      (node (ref "C12") (pin "+") (pinfunction "+_+") (pintype "passive"))
      (node (ref "C13") (pin "1") (pinfunction "1_1") (pintype "passive"))
      (node (ref "C19") (pin "1") (pinfunction "1_1") (pintype "passive"))
      (node (ref "C30") (pin "1") (pinfunction "1_1") (pintype "passive"))
      (node (ref "C31") (pin "1") (pinfunction "1_1") (pintype "passive"))
      (node (ref "C37") (pin "1") (pinfunction "1_1") (pintype "passive"))
      (node (ref "C41") (pin "+") (pinfunction "+_+") (pintype "passive"))
      (node (ref "C44") (pin "1") (pinfunction "1_1") (pintype "passive"))
      (node (ref "C46") (pin "+") (pinfunction "+_+") (pintype "passive"))
      (node (ref "C47") (pin "1") (pinfunction "1_1") (pintype "passive"))
      (node (ref "C48") (pin "1") (pinfunction "1_1") (pintype "passive"))
      (node (ref "C7") (pin "1") (pinfunction "1_1") (pintype "passive"))
      (node (ref "C9") (pin "1") (pinfunction "1_1") (pintype "passive"))
      (node (ref "IC2") (pin "13") (pinfunction "VDDA_13") (pintype "power_in"))
      (node (ref "IC4") (pin "16") (pinfunction "VCC_16") (pintype "power_in"))
      (node (ref "IC5") (pin "8") (pinfunction "V+_8") (pintype "power_in"))
      (node (ref "IC6") (pin "14") (pinfunction "AVDD_14") (pintype "bidirectional"))
      (node (ref "IC6") (pin "8") (pinfunction "HPVDD_8") (pintype "bidirectional"))
      (node (ref "IC7") (pin "4") (pinfunction "V+_4") (pintype "power_in"))
      (node (ref "L3") (pin "2") (pinfunction "2_2") (pintype "passive"))
      (node (ref "R10") (pin "P$1") (pinfunction "E_P$1") (pintype "passive"))
      (node (ref "R28") (pin "P$1") (pinfunction "E_P$1") (pintype "passive"))
      (node (ref "R29") (pin "P$1") (pinfunction "E_P$1") (pintype "passive"))
      (node (ref "R30") (pin "P$1") (pinfunction "E_P$1") (pintype "passive"))
      (node (ref "R45") (pin "P$1") (pinfunction "E_P$1") (pintype "passive"))
      (node (ref "R46") (pin "P$1") (pinfunction "E_P$1") (pintype "passive"))
      (node (ref "R47") (pin "P$1") (pinfunction "E_P$1") (pintype "passive"))
      (node (ref "R48") (pin "P$1") (pinfunction "E_P$1") (pintype "passive"))
      (node (ref "R49") (pin "P$1") (pinfunction "E_P$1") (pintype "passive"))
      (node (ref "R50") (pin "2") (pinfunction "2_2") (pintype "passive"))
      (node (ref "R9") (pin "P$1") (pinfunction "E_P$1") (pintype "passive"))
    )
    (net (code "3") (name "AREF_-10") (class "Default")
      (node (ref "C15") (pin "1") (pinfunction "1_1") (pintype "passive"))
      (node (ref "IC3") (pin "2") (pinfunction "A_2") (pintype "passive"))
      (node (ref "R12") (pin "2") (pinfunction "2_2") (pintype "passive"))
      (node (ref "R15") (pin "2") (pinfunction "2_2") (pintype "passive"))
      (node (ref "R20") (pin "2") (pinfunction "2_2") (pintype "passive"))
      (node (ref "R23") (pin "2") (pinfunction "2_2") (pintype "passive"))
      (node (ref "R24") (pin "2") (pinfunction "2_2") (pintype "passive"))
      (node (ref "R36") (pin "2") (pinfunction "2_2") (pintype "passive"))
      (node (ref "R37") (pin "2") (pinfunction "2_2") (pintype "passive"))
    )
    (net (code "4") (name "AUX_OUT") (class "Default")
      (node (ref "C33") (pin "+") (pinfunction "+_+") (pintype "passive"))
      (node (ref "IC6") (pin "13") (pinfunction "ROUT_13") (pintype "bidirectional"))
    )
    (net (code "5") (name "BOOT_FLASH") (class "Default")
      (node (ref "IC2") (pin "60") (pinfunction "BOOT0_60") (pintype "bidirectional"))
      (node (ref "R7") (pin "2") (pinfunction "2_2") (pintype "passive"))
      (node (ref "SW4") (pin "A") (pinfunction "P_A") (pintype "passive"))
      (node (ref "SW4") (pin "A'") (pinfunction "P1_A'") (pintype "passive"))
    )
    (net (code "6") (name "BRIGHTNESS_ATT") (class "Default")
      (node (ref "IC4") (pin "2") (pinfunction "X6_2") (pintype "bidirectional"))
      (node (ref "R45") (pin "P$2") (pinfunction "S_P$2") (pintype "passive"))
    )
    (net (code "7") (name "BRIGHTNESS_CV") (class "Default")
      (node (ref "C26") (pin "2") (pinfunction "2_2") (pintype "passive"))
      (node (ref "IC2") (pin "14") (pinfunction "PA0-WKUP/USART2_CTS/UART4_TX/ADC0/TIM2_CH1_ETR_14") (pintype "bidirectional"))
      (node (ref "IC5") (pin "1") (pinfunction "OUT_1") (pintype "output"))
      (node (ref "R18") (pin "1") (pinfunction "1_1") (pintype "passive"))
    )
    (net (code "8") (name "BRIGHTNESS_POT") (class "Default")
      (node (ref "IC4") (pin "4") (pinfunction "X7_4") (pintype "bidirectional"))
      (node (ref "R28") (pin "P$2") (pinfunction "S_P$2") (pintype "passive"))
    )
    (net (code "9") (name "CV_NORMALIZATION") (class "Default")
      (node (ref "J7") (pin "P2") (pinfunction "2_P2") (pintype "passive"))
      (node (ref "R57") (pin "2") (pinfunction "2_2") (pintype "passive"))
    )
    (net (code "10") (name "DAMP_ATT") (class "Default")
      (node (ref "IC4") (pin "13") (pinfunction "X0_13") (pintype "bidirectional"))
      (node (ref "R47") (pin "P$2") (pinfunction "S_P$2") (pintype "passive"))
    )
    (net (code "11") (name "DAMP_CV") (class "Default")
      (node (ref "C28") (pin "2") (pinfunction "2_2") (pintype "passive"))
      (node (ref "IC2") (pin "21") (pinfunction "PA5/SPI1_SCK/ADC5/DAC2_21") (pintype "bidirectional"))
      (node (ref "IC7") (pin "14") (pinfunction "OUT_14") (pintype "output"))
      (node (ref "R25") (pin "1") (pinfunction "1_1") (pintype "passive"))
    )
    (net (code "12") (name "DAMP_POT") (class "Default")
      (node (ref "IC4") (pin "5") (pinfunction "X5_5") (pintype "bidirectional"))
      (node (ref "R29") (pin "P$2") (pinfunction "S_P$2") (pintype "passive"))
    )
    (net (code "13") (name "FM_CV") (class "Default")
      (node (ref "C29") (pin "2") (pinfunction "2_2") (pintype "passive"))
      (node (ref "IC2") (pin "20") (pinfunction "PA4/SPI1_NSS/SPI3_NSS/USART2_CK/I2S3_WS/ADC4/DAC1_20") (pintype "bidirectional"))
      (node (ref "IC7") (pin "8") (pinfunction "OUT_8") (pintype "output"))
      (node (ref "R26") (pin "1") (pinfunction "1_1") (pintype "passive"))
    )
    (net (code "14") (name "FREQUENCY_ATT") (class "Default")
      (node (ref "IC4") (pin "1") (pinfunction "X4_1") (pintype "bidirectional"))
      (node (ref "R46") (pin "P$2") (pinfunction "S_P$2") (pintype "passive"))
    )
    (net (code "15") (name "FREQUENCY_POT") (class "Default")
      (node (ref "IC2") (pin "11") (pinfunction "PC3/SPI2_MOSI/I2S2_SD/ADC13_11") (pintype "bidirectional"))
      (node (ref "R9") (pin "P$2") (pinfunction "S_P$2") (pintype "passive"))
    )
    (net (code "16") (name "GEOMETRY_ATT") (class "Default")
      (node (ref "IC4") (pin "14") (pinfunction "X1_14") (pintype "bidirectional"))
      (node (ref "R48") (pin "P$2") (pinfunction "S_P$2") (pintype "passive"))
    )
    (net (code "17") (name "GEOMETRY_CV") (class "Default")
      (node (ref "C36") (pin "2") (pinfunction "2_2") (pintype "passive"))
      (node (ref "IC2") (pin "22") (pinfunction "PA6/SPI1_MISO/ADC6/TIM3_CH1_22") (pintype "bidirectional"))
      (node (ref "IC7") (pin "1") (pinfunction "OUT_1") (pintype "output"))
      (node (ref "R31") (pin "1") (pinfunction "1_1") (pintype "passive"))
    )
    (net (code "18") (name "GEOMETRY_POT") (class "Default")
      (node (ref "IC2") (pin "10") (pinfunction "PC2/SPI2_MISO/ADC12_10") (pintype "bidirectional"))
      (node (ref "R10") (pin "P$2") (pinfunction "S_P$2") (pintype "passive"))
    )
    (net (code "19") (name "GND") (class "Default")
      (node (ref "C1") (pin "+") (pinfunction "+_+") (pintype "passive"))
      (node (ref "C10") (pin "2") (pinfunction "2_2") (pintype "passive"))
      (node (ref "C11") (pin "2") (pinfunction "2_2") (pintype "passive"))
      (node (ref "C12") (pin "-") (pinfunction "-_-") (pintype "passive"))
      (node (ref "C13") (pin "2") (pinfunction "2_2") (pintype "passive"))
      (node (ref "C15") (pin "2") (pinfunction "2_2") (pintype "passive"))
      (node (ref "C16") (pin "2") (pinfunction "2_2") (pintype "passive"))
      (node (ref "C17") (pin "2") (pinfunction "2_2") (pintype "passive"))
      (node (ref "C18") (pin "2") (pinfunction "2_2") (pintype "passive"))
      (node (ref "C19") (pin "2") (pinfunction "2_2") (pintype "passive"))
      (node (ref "C2") (pin "-") (pinfunction "-_-") (pintype "passive"))
      (node (ref "C20") (pin "2") (pinfunction "2_2") (pintype "passive"))
      (node (ref "C21") (pin "-") (pinfunction "-_-") (pintype "passive"))
      (node (ref "C22") (pin "2") (pinfunction "2_2") (pintype "passive"))
      (node (ref "C23") (pin "1") (pinfunction "1_1") (pintype "passive"))
      (node (ref "C24") (pin "1") (pinfunction "1_1") (pintype "passive"))
      (node (ref "C25") (pin "2") (pinfunction "2_2") (pintype "passive"))
      (node (ref "C27") (pin "2") (pinfunction "2_2") (pintype "passive"))
      (node (ref "C3") (pin "-") (pinfunction "-_-") (pintype "passive"))
      (node (ref "C30") (pin "2") (pinfunction "2_2") (pintype "passive"))
      (node (ref "C31") (pin "2") (pinfunction "2_2") (pintype "passive"))
      (node (ref "C34") (pin "-") (pinfunction "-_-") (pintype "passive"))
      (node (ref "C35") (pin "2") (pinfunction "2_2") (pintype "passive"))
      (node (ref "C37") (pin "2") (pinfunction "2_2") (pintype "passive"))
      (node (ref "C39") (pin "2") (pinfunction "2_2") (pintype "passive"))
      (node (ref "C4") (pin "1") (pinfunction "1_1") (pintype "passive"))
      (node (ref "C41") (pin "-") (pinfunction "-_-") (pintype "passive"))
      (node (ref "C44") (pin "2") (pinfunction "2_2") (pintype "passive"))
      (node (ref "C45") (pin "1") (pinfunction "1_1") (pintype "passive"))
      (node (ref "C46") (pin "-") (pinfunction "-_-") (pintype "passive"))
      (node (ref "C47") (pin "2") (pinfunction "2_2") (pintype "passive"))
      (node (ref "C48") (pin "2") (pinfunction "2_2") (pintype "passive"))
      (node (ref "C49") (pin "2") (pinfunction "2_2") (pintype "passive"))
      (node (ref "C5") (pin "1") (pinfunction "1_1") (pintype "passive"))
      (node (ref "C6") (pin "2") (pinfunction "2_2") (pintype "passive"))
      (node (ref "C7") (pin "2") (pinfunction "2_2") (pintype "passive"))
      (node (ref "C8") (pin "-") (pinfunction "-_-") (pintype "passive"))
      (node (ref "C9") (pin "2") (pinfunction "2_2") (pintype "passive"))
      (node (ref "D3") (pin "1") (pinfunction "A_1") (pintype "passive"))
      (node (ref "IC1") (pin "1") (pinfunction "GND_1") (pintype "power_in"))
      (node (ref "IC2") (pin "12") (pinfunction "VSSA_12") (pintype "power_in"))
      (node (ref "IC2") (pin "18") (pinfunction "VSS_4_18") (pintype "power_in"))
      (node (ref "IC2") (pin "26") (pinfunction "PB0/ADC8/TIM3_CH3_26") (pintype "bidirectional"))
      (node (ref "IC2") (pin "28") (pinfunction "PB2/BOOT1_28") (pintype "bidirectional"))
      (node (ref "IC2") (pin "63") (pinfunction "VSS_3_63") (pintype "power_in"))
      (node (ref "IC3") (pin "1") (pinfunction "C_1") (pintype "passive"))
      (node (ref "IC4") (pin "6") (pinfunction "INH_6") (pintype "input"))
      (node (ref "IC4") (pin "7") (pinfunction "VEE_7") (pintype "power_in"))
      (node (ref "IC4") (pin "8") (pinfunction "GND_8") (pintype "power_in"))
      (node (ref "IC5") (pin "3") (pinfunction "+IN_3") (pintype "input"))
      (node (ref "IC5") (pin "4") (pinfunction "V-_4") (pintype "power_in"))
      (node (ref "IC5") (pin "5") (pinfunction "+IN_5") (pintype "input"))
      (node (ref "IC6") (pin "11") (pinfunction "HPGND_11") (pintype "bidirectional"))
      (node (ref "IC6") (pin "15") (pinfunction "AGND_15") (pintype "bidirectional"))
      (node (ref "IC6") (pin "21") (pinfunction "MODE_21") (pintype "bidirectional"))
      (node (ref "IC6") (pin "22") (pinfunction "CSB_22") (pintype "bidirectional"))
      (node (ref "IC6") (pin "28") (pinfunction "DGND_28") (pintype "bidirectional"))
      (node (ref "IC7") (pin "10") (pinfunction "+IN_10") (pintype "input"))
      (node (ref "IC7") (pin "11") (pinfunction "V-_11") (pintype "power_in"))
      (node (ref "IC7") (pin "12") (pinfunction "+IN_12") (pintype "input"))
      (node (ref "IC7") (pin "3") (pinfunction "+IN_3") (pintype "input"))
      (node (ref "IC7") (pin "5") (pinfunction "+IN_5") (pintype "input"))
      (node (ref "IC8") (pin "3") (pinfunction "+IN_3") (pintype "input"))
      (node (ref "IC8") (pin "5") (pinfunction "+IN_5") (pintype "input"))
      (node (ref "J1") (pin "P1") (pinfunction "1_P1") (pintype "passive"))
      (node (ref "J10") (pin "P1") (pinfunction "1_P1") (pintype "passive"))
      (node (ref "J2") (pin "P1") (pinfunction "1_P1") (pintype "passive"))
      (node (ref "J3") (pin "P1") (pinfunction "1_P1") (pintype "passive"))
      (node (ref "J4") (pin "P1") (pinfunction "1_P1") (pintype "passive"))
      (node (ref "J5") (pin "P1") (pinfunction "1_P1") (pintype "passive"))
      (node (ref "J6") (pin "P1") (pinfunction "1_P1") (pintype "passive"))
      (node (ref "J7") (pin "P1") (pinfunction "1_P1") (pintype "passive"))
      (node (ref "J8") (pin "P1") (pinfunction "1_P1") (pintype "passive"))
      (node (ref "J9") (pin "P1") (pinfunction "1_P1") (pintype "passive"))
      (node (ref "JP1") (pin "3") (pinfunction "3_3") (pintype "passive"))
      (node (ref "JP1") (pin "5") (pinfunction "5_5") (pintype "passive"))
      (node (ref "JP1") (pin "9") (pinfunction "9_9") (pintype "passive"))
      (node (ref "JP2") (pin "1") (pinfunction "1_1") (pintype "passive"))
      (node (ref "JP3") (pin "3") (pinfunction "3_3") (pintype "passive"))
      (node (ref "JP3") (pin "4") (pinfunction "4_4") (pintype "passive"))
      (node (ref "JP3") (pin "5") (pinfunction "5_5") (pintype "passive"))
      (node (ref "JP3") (pin "6") (pinfunction "6_6") (pintype "passive"))
      (node (ref "JP3") (pin "7") (pinfunction "7_7") (pintype "passive"))
      (node (ref "JP3") (pin "8") (pinfunction "8_8") (pintype "passive"))
      (node (ref "LED1") (pin "2") (pinfunction "C_2") (pintype "bidirectional"))
      (node (ref "LED2") (pin "2") (pinfunction "C_2") (pintype "bidirectional"))
      (node (ref "Q2") (pin "E") (pinfunction "E_E") (pintype "passive"))
      (node (ref "R10") (pin "P$3") (pinfunction "A_P$3") (pintype "passive"))
      (node (ref "R27") (pin "2") (pinfunction "2_2") (pintype "passive"))
      (node (ref "R28") (pin "P$3") (pinfunction "A_P$3") (pintype "passive"))
      (node (ref "R29") (pin "P$3") (pinfunction "A_P$3") (pintype "passive"))
      (node (ref "R30") (pin "P$3") (pinfunction "A_P$3") (pintype "passive"))
      (node (ref "R33") (pin "1") (pinfunction "1_1") (pintype "passive"))
      (node (ref "R38") (pin "1") (pinfunction "1_1") (pintype "passive"))
      (node (ref "R45") (pin "P$3") (pinfunction "A_P$3") (pintype "passive"))
      (node (ref "R46") (pin "P$3") (pinfunction "A_P$3") (pintype "passive"))
      (node (ref "R47") (pin "P$3") (pinfunction "A_P$3") (pintype "passive"))
      (node (ref "R48") (pin "P$3") (pinfunction "A_P$3") (pintype "passive"))
      (node (ref "R49") (pin "P$3") (pinfunction "A_P$3") (pintype "passive"))
      (node (ref "R51") (pin "1") (pinfunction "1_1") (pintype "passive"))
      (node (ref "R7") (pin "1") (pinfunction "1_1") (pintype "passive"))
      (node (ref "R9") (pin "P$3") (pinfunction "A_P$3") (pintype "passive"))
      (node (ref "SW1") (pin "1") (pinfunction "1_1") (pintype "passive"))
      (node (ref "SW1") (pin "2") (pinfunction "2_2") (pintype "passive"))
      (node (ref "SW2") (pin "1") (pinfunction "1_1") (pintype "passive"))
      (node (ref "SW2") (pin "2") (pinfunction "2_2") (pintype "passive"))
      (node (ref "SW3") (pin "A") (pinfunction "P_A") (pintype "passive"))
      (node (ref "SW3") (pin "A'") (pinfunction "P1_A'") (pintype "passive"))
    )
    (net (code "20") (name "I2C_SCL") (class "Default")
      (node (ref "IC2") (pin "29") (pinfunction "PB10/SPI2_SCK/I2S_SCK/I2C2_SCL/USART3_TX_29") (pintype "bidirectional"))
      (node (ref "IC6") (pin "24") (pinfunction "SCLK_24") (pintype "bidirectional"))
      (node (ref "R16") (pin "1") (pinfunction "1_1") (pintype "passive"))
    )
    (net (code "21") (name "I2C_SDA") (class "Default")
      (node (ref "IC2") (pin "30") (pinfunction "PB11/I2C2_SDA/USART3_RX_30") (pintype "bidirectional"))
      (node (ref "IC6") (pin "23") (pinfunction "SDIN_23") (pintype "bidirectional"))
      (node (ref "R17") (pin "1") (pinfunction "1_1") (pintype "passive"))
    )
    (net (code "22") (name "I2S_LRCK") (class "Default")
      (node (ref "IC2") (pin "33") (pinfunction "PB12/SPI2_NSS/I2S2_WS/I2C2_SMBA/USART3_CK/TIM1_BKIN_33") (pintype "bidirectional"))
      (node (ref "IC6") (pin "5") (pinfunction "DACLRC_5") (pintype "bidirectional"))
      (node (ref "IC6") (pin "7") (pinfunction "ADCLRC_7") (pintype "bidirectional"))
    )
    (net (code "23") (name "I2S_SCK") (class "Default")
      (node (ref "IC2") (pin "34") (pinfunction "PB13/SPI2_SCK/I2S2_SCK/USART3_CTS/TIM1_CH1N_34") (pintype "bidirectional"))
      (node (ref "IC6") (pin "3") (pinfunction "BCLK_3") (pintype "bidirectional"))
    )
    (net (code "24") (name "I2S_SIN") (class "Default")
      (node (ref "IC2") (pin "35") (pinfunction "PB14/SPI2_MISO/USART3_RTS/TIM1_CH2N_35") (pintype "bidirectional"))
      (node (ref "IC6") (pin "6") (pinfunction "ADCDAT_6") (pintype "bidirectional"))
    )
    (net (code "25") (name "I2S_SOUT") (class "Default")
      (node (ref "IC2") (pin "36") (pinfunction "PB15/SPI2_MOSI/I2S2_SD/TIM1_CH3N_36") (pintype "bidirectional"))
      (node (ref "IC6") (pin "4") (pinfunction "DACDAT_4") (pintype "bidirectional"))
    )
    (net (code "26") (name "IN_1") (class "Default")
      (node (ref "IC6") (pin "20") (pinfunction "LLINEIN_20") (pintype "bidirectional"))
      (node (ref "R27") (pin "1") (pinfunction "1_1") (pintype "passive"))
    )
    (net (code "27") (name "IN_2") (class "Default")
      (node (ref "C40") (pin "+") (pinfunction "+_+") (pintype "passive"))
      (node (ref "IC6") (pin "19") (pinfunction "RLINEIN_19") (pintype "bidirectional"))
    )
    (net (code "28") (name "JTCK") (class "Default")
      (node (ref "IC2") (pin "49") (pinfunction "PA14/JTCK-SWCLK_49") (pintype "bidirectional"))
      (node (ref "JP1") (pin "4") (pinfunction "4_4") (pintype "passive"))
    )
    (net (code "29") (name "JTDI") (class "Default")
      (node (ref "IC2") (pin "50") (pinfunction "PA15/JTDI/SPI3_NSS/I2S3_WS_50") (pintype "bidirectional"))
      (node (ref "JP1") (pin "8") (pinfunction "8_8") (pintype "passive"))
    )
    (net (code "30") (name "JTDO") (class "Default")
      (node (ref "IC2") (pin "55") (pinfunction "PB3/JTDO/SPI3_SCK/I2S3_SCK_55") (pintype "bidirectional"))
      (node (ref "JP1") (pin "6") (pinfunction "6_6") (pintype "passive"))
    )
    (net (code "31") (name "JTMS") (class "Default")
      (node (ref "IC2") (pin "46") (pinfunction "PA13/JTMS-SWDAT_46") (pintype "bidirectional"))
      (node (ref "JP1") (pin "2") (pinfunction "2_2") (pintype "passive"))
    )
    (net (code "32") (name "MAIN_OUT") (class "Default")
      (node (ref "C32") (pin "+") (pinfunction "+_+") (pintype "passive"))
      (node (ref "IC6") (pin "12") (pinfunction "LOUT_12") (pintype "bidirectional"))
    )
    (net (code "33") (name "MUXED_POTS") (class "Default")
      (node (ref "IC2") (pin "9") (pinfunction "PC1/ADC11_9") (pintype "bidirectional"))
      (node (ref "IC4") (pin "3") (pinfunction "X_3") (pintype "bidirectional"))
    )
    (net (code "34") (name "MUX_ADDR_0") (class "Default")
      (node (ref "IC2") (pin "59") (pinfunction "PB7/I2C1_SDA/TIM4_CH2/USART1_RX_59") (pintype "bidirectional"))
      (node (ref "IC4") (pin "11") (pinfunction "A_11") (pintype "input"))
    )
    (net (code "35") (name "MUX_ADDR_1") (class "Default")
      (node (ref "IC2") (pin "58") (pinfunction "PB6/I2C1_SCL/TIM4_CH1/USART1_TX_58") (pintype "bidirectional"))
      (node (ref "IC4") (pin "10") (pinfunction "B_10") (pintype "input"))
    )
    (net (code "36") (name "MUX_ADDR_2") (class "Default")
      (node (ref "IC2") (pin "57") (pinfunction "PB5/I2C1_SMBA/SPI1_MOSI/SPI3_MOSI/I2S3_SD_57") (pintype "bidirectional"))
      (node (ref "IC4") (pin "9") (pinfunction "C_9") (pintype "input"))
    )
    (net (code "37") (name "NORMALIZATION_PROBE") (class "Default")
      (node (ref "D3") (pin "3") (pinfunction "AC_3") (pintype "passive"))
      (node (ref "IC2") (pin "39") (pinfunction "PC8_39") (pintype "bidirectional"))
      (node (ref "R52") (pin "1") (pinfunction "1_1") (pintype "passive"))
      (node (ref "R53") (pin "1") (pinfunction "1_1") (pintype "passive"))
      (node (ref "R57") (pin "1") (pinfunction "1_1") (pintype "passive"))
    )
    (net (code "38") (name "Net-(C32-Pad-)") (class "Default")
      (node (ref "C32") (pin "-") (pinfunction "-_-") (pintype "passive"))
      (node (ref "R33") (pin "2") (pinfunction "2_2") (pintype "passive"))
      (node (ref "R40") (pin "2") (pinfunction "2_2") (pintype "passive"))
    )
    (net (code "39") (name "Net-(C33-Pad-)") (class "Default")
      (node (ref "C33") (pin "-") (pinfunction "-_-") (pintype "passive"))
      (node (ref "R38") (pin "2") (pinfunction "2_2") (pintype "passive"))
      (node (ref "R43") (pin "2") (pinfunction "2_2") (pintype "passive"))
    )
    (net (code "40") (name "Net-(C40-Pad-)") (class "Default")
      (node (ref "C40") (pin "-") (pinfunction "-_-") (pintype "passive"))
      (node (ref "C49") (pin "1") (pinfunction "1_1") (pintype "passive"))
      (node (ref "R51") (pin "2") (pinfunction "2_2") (pintype "passive"))
      (node (ref "R54") (pin "1") (pinfunction "1_1") (pintype "passive"))
    )
    (net (code "41") (name "Net-(D1-PadA)") (class "Default")
      (node (ref "D1") (pin "A") (pinfunction "A_A") (pintype "passive"))
      (node (ref "L1") (pin "1") (pinfunction "1_1") (pintype "passive"))
    )
    (net (code "42") (name "Net-(D2-PadC)") (class "Default")
      (node (ref "D2") (pin "C") (pinfunction "C_C") (pintype "passive"))
      (node (ref "L2") (pin "1") (pinfunction "1_1") (pintype "passive"))
    )
    (net (code "43") (name "Net-(IC1-VIN)") (class "Default")
      (node (ref "C2") (pin "+") (pinfunction "+_+") (pintype "passive"))
      (node (ref "IC1") (pin "2") (pinfunction "VIN_2") (pintype "input"))
      (node (ref "R2") (pin "1") (pinfunction "1_1") (pintype "passive"))
    )
    (net (code "44") (name "Net-(IC2-PC0{slash}ADC10)") (class "Default")
      (node (ref "IC2") (pin "8") (pinfunction "PC0/ADC10_8") (pintype "bidirectional"))
      (node (ref "R4") (pin "1") (pinfunction "1_1") (pintype "passive"))
    )
    (net (code "45") (name "Net-(IC2-PC10{slash}SPI3_SCK{slash}I2S3_SCK{slash}UART4_TX)") (class "Default")
      (node (ref "IC2") (pin "51") (pinfunction "PC10/SPI3_SCK/I2S3_SCK/UART4_TX_51") (pintype "bidirectional"))
      (node (ref "R5") (pin "1") (pinfunction "1_1") (pintype "passive"))
    )
    (net (code "46") (name "Net-(IC2-PC11{slash}UART4_RX{slash}SPI3_MISO{slash}USART3_RX)") (class "Default")
      (node (ref "IC2") (pin "52") (pinfunction "PC11/UART4_RX/SPI3_MISO/USART3_RX_52") (pintype "bidirectional"))
      (node (ref "R3") (pin "1") (pinfunction "1_1") (pintype "passive"))
    )
    (net (code "47") (name "Net-(IC2-PC12{slash}UART5_TX{slash}I2S3_SD{slash}USART3_CK)") (class "Default")
      (node (ref "IC2") (pin "53") (pinfunction "PC12/UART5_TX/I2S3_SD/USART3_CK_53") (pintype "bidirectional"))
      (node (ref "R1") (pin "1") (pinfunction "1_1") (pintype "passive"))
    )
    (net (code "48") (name "Net-(IC2-PD0{slash}OSC_IN)") (class "Default")
      (node (ref "C5") (pin "2") (pinfunction "2_2") (pintype "passive"))
      (node (ref "IC2") (pin "5") (pinfunction "PD0/OSC_IN_5") (pintype "bidirectional"))
      (node (ref "Q1") (pin "2") (pinfunction "2_2") (pintype "passive"))
    )
    (net (code "49") (name "Net-(IC2-PD1{slash}OSC_OUT)") (class "Default")
      (node (ref "C4") (pin "2") (pinfunction "2_2") (pintype "passive"))
      (node (ref "IC2") (pin "6") (pinfunction "PD1/OSC_OUT_6") (pintype "bidirectional"))
      (node (ref "Q1") (pin "1") (pinfunction "1_1") (pintype "passive"))
    )
    (net (code "50") (name "Net-(IC2-VCAP_1)") (class "Default")
      (node (ref "C16") (pin "1") (pinfunction "1_1") (pintype "passive"))
      (node (ref "IC2") (pin "31") (pinfunction "VCAP_1_31") (pintype "power_in"))
    )
    (net (code "51") (name "Net-(IC2-VCAP_2)") (class "Default")
      (node (ref "C22") (pin "1") (pinfunction "1_1") (pintype "passive"))
      (node (ref "IC2") (pin "47") (pinfunction "VCAP_2_47") (pintype "power_in"))
    )
    (net (code "52") (name "Net-(IC5A--IN)") (class "Default")
      (node (ref "C26") (pin "1") (pinfunction "1_1") (pintype "passive"))
      (node (ref "IC5") (pin "2") (pinfunction "-IN_2") (pintype "input"))
      (node (ref "R18") (pin "2") (pinfunction "2_2") (pintype "passive"))
      (node (ref "R19") (pin "1") (pinfunction "1_1") (pintype "passive"))
      (node (ref "R20") (pin "1") (pinfunction "1_1") (pintype "passive"))
    )
    (net (code "53") (name "Net-(IC5B--IN)") (class "Default")
      (node (ref "C14") (pin "1") (pinfunction "1_1") (pintype "passive"))
      (node (ref "IC5") (pin "6") (pinfunction "-IN_6") (pintype "input"))
      (node (ref "R13") (pin "2") (pinfunction "2_2") (pintype "passive"))
      (node (ref "R14") (pin "1") (pinfunction "1_1") (pintype "passive"))
      (node (ref "R15") (pin "1") (pinfunction "1_1") (pintype "passive"))
    )
    (net (code "54") (name "Net-(IC6-VMID)") (class "Default")
      (node (ref "C34") (pin "+") (pinfunction "+_+") (pintype "passive"))
      (node (ref "C35") (pin "1") (pinfunction "1_1") (pintype "passive"))
      (node (ref "IC6") (pin "16") (pinfunction "VMID_16") (pintype "bidirectional"))
    )
    (net (code "55") (name "Net-(IC6-XTI{slash}MCLK)") (class "Default")
      (node (ref "C24") (pin "2") (pinfunction "2_2") (pintype "passive"))
      (node (ref "IC6") (pin "25") (pinfunction "XTI/MCLK_25") (pintype "bidirectional"))
      (node (ref "Q3") (pin "2") (pinfunction "2_2") (pintype "passive"))
    )
    (net (code "56") (name "Net-(IC6-XTO)") (class "Default")
      (node (ref "C23") (pin "2") (pinfunction "2_2") (pintype "passive"))
      (node (ref "IC6") (pin "26") (pinfunction "XTO_26") (pintype "bidirectional"))
      (node (ref "Q3") (pin "1") (pinfunction "1_1") (pintype "passive"))
    )
    (net (code "57") (name "Net-(IC7A--IN)") (class "Default")
      (node (ref "C36") (pin "1") (pinfunction "1_1") (pintype "passive"))
      (node (ref "IC7") (pin "2") (pinfunction "-IN_2") (pintype "input"))
      (node (ref "R31") (pin "2") (pinfunction "2_2") (pintype "passive"))
      (node (ref "R34") (pin "1") (pinfunction "1_1") (pintype "passive"))
      (node (ref "R36") (pin "1") (pinfunction "1_1") (pintype "passive"))
    )
    (net (code "58") (name "Net-(IC7B--IN)") (class "Default")
      (node (ref "C38") (pin "1") (pinfunction "1_1") (pintype "passive"))
      (node (ref "IC7") (pin "6") (pinfunction "-IN_6") (pintype "input"))
      (node (ref "R32") (pin "2") (pinfunction "2_2") (pintype "passive"))
      (node (ref "R35") (pin "1") (pinfunction "1_1") (pintype "passive"))
      (node (ref "R37") (pin "1") (pinfunction "1_1") (pintype "passive"))
    )
    (net (code "59") (name "Net-(IC7C--IN)") (class "Default")
      (node (ref "C29") (pin "1") (pinfunction "1_1") (pintype "passive"))
      (node (ref "IC7") (pin "9") (pinfunction "-IN_9") (pintype "input"))
      (node (ref "R22") (pin "1") (pinfunction "1_1") (pintype "passive"))
      (node (ref "R24") (pin "1") (pinfunction "1_1") (pintype "passive"))
      (node (ref "R26") (pin "2") (pinfunction "2_2") (pintype "passive"))
    )
    (net (code "60") (name "Net-(IC7D--IN)") (class "Default")
      (node (ref "C28") (pin "1") (pinfunction "1_1") (pintype "passive"))
      (node (ref "IC7") (pin "13") (pinfunction "-IN_13") (pintype "input"))
      (node (ref "R21") (pin "1") (pinfunction "1_1") (pintype "passive"))
      (node (ref "R23") (pin "1") (pinfunction "1_1") (pintype "passive"))
      (node (ref "R25") (pin "2") (pinfunction "2_2") (pintype "passive"))
    )
    (net (code "61") (name "Net-(IC8A--IN)") (class "Default")
      (node (ref "C42") (pin "1") (pinfunction "1_1") (pintype "passive"))
      (node (ref "IC8") (pin "2") (pinfunction "-IN_2") (pintype "input"))
      (node (ref "R39") (pin "1") (pinfunction "1_1") (pintype "passive"))
      (node (ref "R40") (pin "1") (pinfunction "1_1") (pintype "passive"))
      (node (ref "R41") (pin "2") (pinfunction "2_2") (pintype "passive"))
    )
    (net (code "62") (name "Net-(IC8A-OUT)") (class "Default")
      (node (ref "C42") (pin "2") (pinfunction "2_2") (pintype "passive"))
      (node (ref "IC8") (pin "1") (pinfunction "OUT_1") (pintype "output"))
      (node (ref "R41") (pin "1") (pinfunction "1_1") (pintype "passive"))
      (node (ref "R55") (pin "2") (pinfunction "2_2") (pintype "passive"))
    )
    (net (code "63") (name "Net-(IC8B--IN)") (class "Default")
      (node (ref "C43") (pin "1") (pinfunction "1_1") (pintype "passive"))
      (node (ref "IC8") (pin "6") (pinfunction "-IN_6") (pintype "input"))
      (node (ref "R42") (pin "2") (pinfunction "2_2") (pintype "passive"))
      (node (ref "R43") (pin "1") (pinfunction "1_1") (pintype "passive"))
      (node (ref "R44") (pin "1") (pinfunction "1_1") (pintype "passive"))
    )
    (net (code "64") (name "Net-(IC8B-OUT)") (class "Default")
      (node (ref "C43") (pin "2") (pinfunction "2_2") (pintype "passive"))
      (node (ref "IC8") (pin "7") (pinfunction "OUT_7") (pintype "output"))
      (node (ref "R42") (pin "1") (pinfunction "1_1") (pintype "passive"))
      (node (ref "R56") (pin "2") (pinfunction "2_2") (pintype "passive"))
    )
    (net (code "65") (name "Net-(J1-3)") (class "Default")
      (node (ref "J1") (pin "P3") (pinfunction "3_P3") (pintype "passive"))
      (node (ref "R19") (pin "2") (pinfunction "2_2") (pintype "passive"))
    )
    (net (code "66") (name "Net-(J2-2)") (class "Default")
      (node (ref "J2") (pin "P2") (pinfunction "2_P2") (pintype "passive"))
      (node (ref "R50") (pin "1") (pinfunction "1_1") (pintype "passive"))
    )
    (net (code "67") (name "Net-(J2-3)") (class "Default")
      (node (ref "J2") (pin "P3") (pinfunction "3_P3") (pintype "passive"))
      (node (ref "R22") (pin "2") (pinfunction "2_2") (pintype "passive"))
    )
    (net (code "68") (name "Net-(J3-3)") (class "Default")
      (node (ref "J3") (pin "P3") (pinfunction "3_P3") (pintype "passive"))
      (node (ref "R21") (pin "2") (pinfunction "2_2") (pintype "passive"))
    )
    (net (code "69") (name "Net-(J4-3)") (class "Default")
      (node (ref "J4") (pin "P3") (pinfunction "3_P3") (pintype "passive"))
      (node (ref "R34") (pin "2") (pinfunction "2_2") (pintype "passive"))
    )
    (net (code "70") (name "Net-(J5-3)") (class "Default")
      (node (ref "J5") (pin "P3") (pinfunction "3_P3") (pintype "passive"))
      (node (ref "R35") (pin "2") (pinfunction "2_2") (pintype "passive"))
    )
    (net (code "71") (name "Net-(J6-2)") (class "Default")
      (node (ref "J6") (pin "P2") (pinfunction "2_P2") (pintype "passive"))
      (node (ref "R52") (pin "2") (pinfunction "2_2") (pintype "passive"))
    )
    (net (code "72") (name "Net-(J6-3)") (class "Default")
      (node (ref "J6") (pin "P3") (pinfunction "3_P3") (pintype "passive"))
      (node (ref "R11") (pin "1") (pinfunction "1_1") (pintype "passive"))
    )
    (net (code "73") (name "Net-(J7-3)") (class "Default")
      (node (ref "J7") (pin "P3") (pinfunction "3_P3") (pintype "passive"))
      (node (ref "R14") (pin "2") (pinfunction "2_2") (pintype "passive"))
    )
    (net (code "74") (name "Net-(J8-2)") (class "Default")
      (node (ref "J8") (pin "P2") (pinfunction "2_P2") (pintype "passive"))
      (node (ref "R53") (pin "2") (pinfunction "2_2") (pintype "passive"))
    )
    (net (code "75") (name "Net-(J8-3)") (class "Default")
      (node (ref "J8") (pin "P3") (pinfunction "3_P3") (pintype "passive"))
      (node (ref "R54") (pin "2") (pinfunction "2_2") (pintype "passive"))
    )
    (net (code "76") (name "Net-(J9-2)") (class "Default")
      (node (ref "J9") (pin "P2") (pinfunction "2_P2") (pintype "passive"))
      (node (ref "SJ1") (pin "2") (pinfunction "2_2") (pintype "passive"))
    )
    (net (code "77") (name "Net-(J9-3)") (class "Default")
      (node (ref "J9") (pin "P3") (pinfunction "3_P3") (pintype "passive"))
      (node (ref "R55") (pin "1") (pinfunction "1_1") (pintype "passive"))
    )
    (net (code "78") (name "Net-(J10-2)") (class "Default")
      (node (ref "J10") (pin "P2") (pinfunction "2_P2") (pintype "passive"))
      (node (ref "R39") (pin "2") (pinfunction "2_2") (pintype "passive"))
    )
    (net (code "79") (name "Net-(J10-3)") (class "Default")
      (node (ref "J10") (pin "P3") (pinfunction "3_P3") (pintype "passive"))
      (node (ref "R56") (pin "1") (pinfunction "1_1") (pintype "passive"))
    )
    (net (code "80") (name "Net-(JP3-Pad1)") (class "Default")
      (node (ref "JP3") (pin "1") (pinfunction "1_1") (pintype "passive"))
      (node (ref "JP3") (pin "2") (pinfunction "2_2") (pintype "passive"))
      (node (ref "L1") (pin "2") (pinfunction "2_2") (pintype "passive"))
    )
    (net (code "81") (name "Net-(JP3-Pad10)") (class "Default")
      (node (ref "JP3") (pin "10") (pinfunction "10_10") (pintype "passive"))
      (node (ref "JP3") (pin "9") (pinfunction "9_9") (pintype "passive"))
      (node (ref "L2") (pin "2") (pinfunction "2_2") (pintype "passive"))
    )
    (net (code "82") (name "Net-(LED1-GRN)") (class "Default")
      (node (ref "LED1") (pin "1") (pinfunction "GRN_1") (pintype "bidirectional"))
      (node (ref "R3") (pin "2") (pinfunction "2_2") (pintype "passive"))
    )
    (net (code "83") (name "Net-(LED1-RED)") (class "Default")
      (node (ref "LED1") (pin "3") (pinfunction "RED_3") (pintype "bidirectional"))
      (node (ref "R1") (pin "2") (pinfunction "2_2") (pintype "passive"))
    )
    (net (code "84") (name "Net-(LED2-GRN)") (class "Default")
      (node (ref "LED2") (pin "1") (pinfunction "GRN_1") (pintype "bidirectional"))
      (node (ref "R5") (pin "2") (pinfunction "2_2") (pintype "passive"))
    )
    (net (code "85") (name "Net-(LED2-RED)") (class "Default")
      (node (ref "LED2") (pin "3") (pinfunction "RED_3") (pintype "bidirectional"))
      (node (ref "R4") (pin "2") (pinfunction "2_2") (pintype "passive"))
    )
    (net (code "86") (name "Net-(Q2-PadB)") (class "Default")
      (node (ref "Q2") (pin "B") (pinfunction "B_B") (pintype "passive"))
      (node (ref "R11") (pin "2") (pinfunction "2_2") (pintype "passive"))
    )
    (net (code "87") (name "Net-(R44-Pad2)") (class "Default")
      (node (ref "R44") (pin "2") (pinfunction "2_2") (pintype "passive"))
      (node (ref "SJ1") (pin "1") (pinfunction "1_1") (pintype "passive"))
    )
    (net (code "88") (name "POSITION_ATT") (class "Default")
      (node (ref "IC4") (pin "15") (pinfunction "X2_15") (pintype "bidirectional"))
      (node (ref "R49") (pin "P$2") (pinfunction "S_P$2") (pintype "passive"))
    )
    (net (code "89") (name "POSITION_CV") (class "Default")
      (node (ref "C38") (pin "2") (pinfunction "2_2") (pintype "passive"))
      (node (ref "IC2") (pin "23") (pinfunction "PA7/SPI1_MOSI/ADC7/TIM3_CH2_23") (pintype "bidirectional"))
      (node (ref "IC7") (pin "7") (pinfunction "OUT_7") (pintype "output"))
      (node (ref "R32") (pin "1") (pinfunction "1_1") (pintype "passive"))
    )
    (net (code "90") (name "POSITION_POT") (class "Default")
      (node (ref "IC4") (pin "12") (pinfunction "X3_12") (pintype "bidirectional"))
      (node (ref "R30") (pin "P$2") (pinfunction "S_P$2") (pintype "passive"))
    )
    (net (code "91") (name "RESET") (class "Default")
      (node (ref "IC2") (pin "7") (pinfunction "NRST_7") (pintype "bidirectional"))
      (node (ref "JP1") (pin "10") (pinfunction "10_10") (pintype "passive"))
      (node (ref "R6") (pin "1") (pinfunction "1_1") (pintype "passive"))
      (node (ref "SW3") (pin "B") (pinfunction "S_B") (pintype "passive"))
      (node (ref "SW3") (pin "B'") (pinfunction "S1_B'") (pintype "passive"))
    )
    (net (code "92") (name "RX") (class "Default")
      (node (ref "IC2") (pin "43") (pinfunction "PA10/USART1_RX/TIM1_CH3_43") (pintype "bidirectional"))
      (node (ref "JP2") (pin "4") (pinfunction "4_4") (pintype "passive"))
    )
    (net (code "93") (name "STRUM") (class "Default")
      (node (ref "IC2") (pin "16") (pinfunction "PA2/USART2_TX/ADC2/TIM2_CH3_16") (pintype "bidirectional"))
      (node (ref "Q2") (pin "C") (pinfunction "C_C") (pintype "passive"))
      (node (ref "R8") (pin "1") (pinfunction "1_1") (pintype "passive"))
    )
    (net (code "94") (name "SW_MODE") (class "Default")
      (node (ref "IC2") (pin "61") (pinfunction "PB8/TIM4_CH3/I2C1_SCL_61") (pintype "bidirectional"))
      (node (ref "SW2") (pin "3") (pinfunction "3_3") (pintype "passive"))
      (node (ref "SW2") (pin "4") (pinfunction "4_4") (pintype "passive"))
    )
    (net (code "95") (name "SW_POLYPHONY") (class "Default")
      (node (ref "IC2") (pin "62") (pinfunction "PB9/SPI2_NSS/I2S2_WS/I2C1_SDA/TIM4_CH4_62") (pintype "bidirectional"))
      (node (ref "SW1") (pin "3") (pinfunction "3_3") (pintype "passive"))
      (node (ref "SW1") (pin "4") (pinfunction "4_4") (pintype "passive"))
    )
    (net (code "96") (name "TX") (class "Default")
      (node (ref "IC2") (pin "42") (pinfunction "PA9/USART1_TX/TIM1_CH2_42") (pintype "bidirectional"))
      (node (ref "JP2") (pin "5") (pinfunction "5_5") (pintype "passive"))
    )
    (net (code "97") (name "VBAT") (class "Default")
      (node (ref "IC2") (pin "1") (pinfunction "VBAT_1") (pintype "power_in"))
    )
    (net (code "98") (name "VCC") (class "Default")
      (node (ref "C3") (pin "+") (pinfunction "+_+") (pintype "passive"))
      (node (ref "C39") (pin "1") (pinfunction "1_1") (pintype "passive"))
      (node (ref "D1") (pin "C") (pinfunction "C_C") (pintype "passive"))
      (node (ref "IC8") (pin "8") (pinfunction "V+_8") (pintype "power_in"))
      (node (ref "R2") (pin "2") (pinfunction "2_2") (pintype "passive"))
    )
    (net (code "99") (name "VEE") (class "Default")
      (node (ref "C1") (pin "-") (pinfunction "-_-") (pintype "passive"))
      (node (ref "C45") (pin "2") (pinfunction "2_2") (pintype "passive"))
      (node (ref "D2") (pin "A") (pinfunction "A_A") (pintype "passive"))
      (node (ref "IC8") (pin "4") (pinfunction "V-_4") (pintype "power_in"))
      (node (ref "R12") (pin "1") (pinfunction "1_1") (pintype "passive"))
    )
    (net (code "100") (name "V_OCT_CV") (class "Default")
      (node (ref "C14") (pin "2") (pinfunction "2_2") (pintype "passive"))
      (node (ref "IC2") (pin "15") (pinfunction "PA1/USART2_RTS/UART4_RX/ADC1/TIM2_CH2_15") (pintype "bidirectional"))
      (node (ref "IC5") (pin "7") (pinfunction "OUT_7") (pintype "output"))
      (node (ref "R13") (pin "1") (pinfunction "1_1") (pintype "passive"))
    )
    (net (code "101") (name "unconnected-(IC2-PA3{slash}USART2_RX{slash}ADC3{slash}TIM2_CH4-Pad17)") (class "Default")
      (node (ref "IC2") (pin "17") (pinfunction "PA3/USART2_RX/ADC3/TIM2_CH4_17") (pintype "bidirectional"))
    )
    (net (code "102") (name "unconnected-(IC2-PA8{slash}USART1_CK{slash}TIM1_CH1{slash}MCO-Pad41)") (class "Default")
      (node (ref "IC2") (pin "41") (pinfunction "PA8/USART1_CK/TIM1_CH1/MCO_41") (pintype "bidirectional"))
    )
    (net (code "103") (name "unconnected-(IC2-PA11{slash}USART1_CTS{slash}CANRX{slash}USBDM{slash}TIM1_CH4-Pad44)") (class "Default")
      (node (ref "IC2") (pin "44") (pinfunction "PA11/USART1_CTS/CANRX/USBDM/TIM1_CH4_44") (pintype "bidirectional"))
    )
    (net (code "104") (name "unconnected-(IC2-PA12{slash}USART1_RTS{slash}CANTX{slash}USBDP{slash}TIM1_ETR-Pad45)") (class "Default")
      (node (ref "IC2") (pin "45") (pinfunction "PA12/USART1_RTS/CANTX/USBDP/TIM1_ETR_45") (pintype "bidirectional"))
    )
    (net (code "105") (name "unconnected-(IC2-PB1{slash}ADC9{slash}TIM3_CH4-Pad27)") (class "Default")
      (node (ref "IC2") (pin "27") (pinfunction "PB1/ADC9/TIM3_CH4_27") (pintype "bidirectional"))
    )
    (net (code "106") (name "unconnected-(IC2-PB4{slash}NJTRST{slash}SPI3_MISO{slash}SPI1_MISO-Pad56)") (class "Default")
      (node (ref "IC2") (pin "56") (pinfunction "PB4/NJTRST/SPI3_MISO/SPI1_MISO_56") (pintype "bidirectional"))
    )
    (net (code "107") (name "unconnected-(IC2-PC4{slash}ADC14-Pad24)") (class "Default")
      (node (ref "IC2") (pin "24") (pinfunction "PC4/ADC14_24") (pintype "bidirectional"))
    )
    (net (code "108") (name "unconnected-(IC2-PC5{slash}ADC15-Pad25)") (class "Default")
      (node (ref "IC2") (pin "25") (pinfunction "PC5/ADC15_25") (pintype "bidirectional"))
    )
    (net (code "109") (name "unconnected-(IC2-PC6{slash}I2S2_MCK-Pad37)") (class "Default")
      (node (ref "IC2") (pin "37") (pinfunction "PC6/I2S2_MCK_37") (pintype "bidirectional"))
    )
    (net (code "110") (name "unconnected-(IC2-PC7{slash}I2S3_MCK-Pad38)") (class "Default")
      (node (ref "IC2") (pin "38") (pinfunction "PC7/I2S3_MCK_38") (pintype "bidirectional"))
    )
    (net (code "111") (name "unconnected-(IC2-PC9{slash}I2S2_CKIN{slash}I2S3_CKIN-Pad40)") (class "Default")
      (node (ref "IC2") (pin "40") (pinfunction "PC9/I2S2_CKIN/I2S3_CKIN_40") (pintype "bidirectional"))
    )
    (net (code "112") (name "unconnected-(IC2-PC13-TAMPER-RTC-Pad2)") (class "Default")
      (node (ref "IC2") (pin "2") (pinfunction "PC13-TAMPER-RTC_2") (pintype "bidirectional"))
    )
    (net (code "113") (name "unconnected-(IC2-PC14{slash}OSC32_IN-Pad3)") (class "Default")
      (node (ref "IC2") (pin "3") (pinfunction "PC14/OSC32_IN_3") (pintype "bidirectional"))
    )
    (net (code "114") (name "unconnected-(IC2-PC15{slash}OSC_OUT-Pad4)") (class "Default")
      (node (ref "IC2") (pin "4") (pinfunction "PC15/OSC_OUT_4") (pintype "bidirectional"))
    )
    (net (code "115") (name "unconnected-(IC2-PD2{slash}TIM3-ETR-Pad54)") (class "Default")
      (node (ref "IC2") (pin "54") (pinfunction "PD2/TIM3-ETR_54") (pintype "bidirectional"))
    )
    (net (code "116") (name "unconnected-(IC6-CLKOUT-Pad2)") (class "Default")
      (node (ref "IC6") (pin "2") (pinfunction "CLKOUT_2") (pintype "bidirectional"))
    )
    (net (code "117") (name "unconnected-(IC6-LHPOUT-Pad9)") (class "Default")
      (node (ref "IC6") (pin "9") (pinfunction "LHPOUT_9") (pintype "bidirectional"))
    )
    (net (code "118") (name "unconnected-(IC6-MICBIAS-Pad17)") (class "Default")
      (node (ref "IC6") (pin "17") (pinfunction "MICBIAS_17") (pintype "bidirectional"))
    )
    (net (code "119") (name "unconnected-(IC6-MICIN-Pad18)") (class "Default")
      (node (ref "IC6") (pin "18") (pinfunction "MICIN_18") (pintype "bidirectional"))
    )
    (net (code "120") (name "unconnected-(IC6-RHPOUT-Pad10)") (class "Default")
      (node (ref "IC6") (pin "10") (pinfunction "RHPOUT_10") (pintype "bidirectional"))
    )
    (net (code "121") (name "unconnected-(J1-2-PadP2)") (class "Default")
      (node (ref "J1") (pin "P2") (pinfunction "2_P2") (pintype "passive"))
    )
    (net (code "122") (name "unconnected-(J3-2-PadP2)") (class "Default")
      (node (ref "J3") (pin "P2") (pinfunction "2_P2") (pintype "passive"))
    )
    (net (code "123") (name "unconnected-(J4-2-PadP2)") (class "Default")
      (node (ref "J4") (pin "P2") (pinfunction "2_P2") (pintype "passive"))
    )
    (net (code "124") (name "unconnected-(J5-2-PadP2)") (class "Default")
      (node (ref "J5") (pin "P2") (pinfunction "2_P2") (pintype "passive"))
    )
    (net (code "125") (name "unconnected-(JP1-Pad7)") (class "Default")
      (node (ref "JP1") (pin "7") (pinfunction "7_7") (pintype "passive"))
    )
    (net (code "126") (name "unconnected-(JP2-Pad2)") (class "Default")
      (node (ref "JP2") (pin "2") (pinfunction "2_2") (pintype "passive"))
    )
    (net (code "127") (name "unconnected-(JP2-Pad3)") (class "Default")
      (node (ref "JP2") (pin "3") (pinfunction "3_3") (pintype "passive"))
    )
    (net (code "128") (name "unconnected-(JP2-Pad6)") (class "Default")
      (node (ref "JP2") (pin "6") (pinfunction "6_6") (pintype "passive"))
    )
  )
)
